# MAIN.net
KiCad netlist of a schematic drawn in Altium Designer
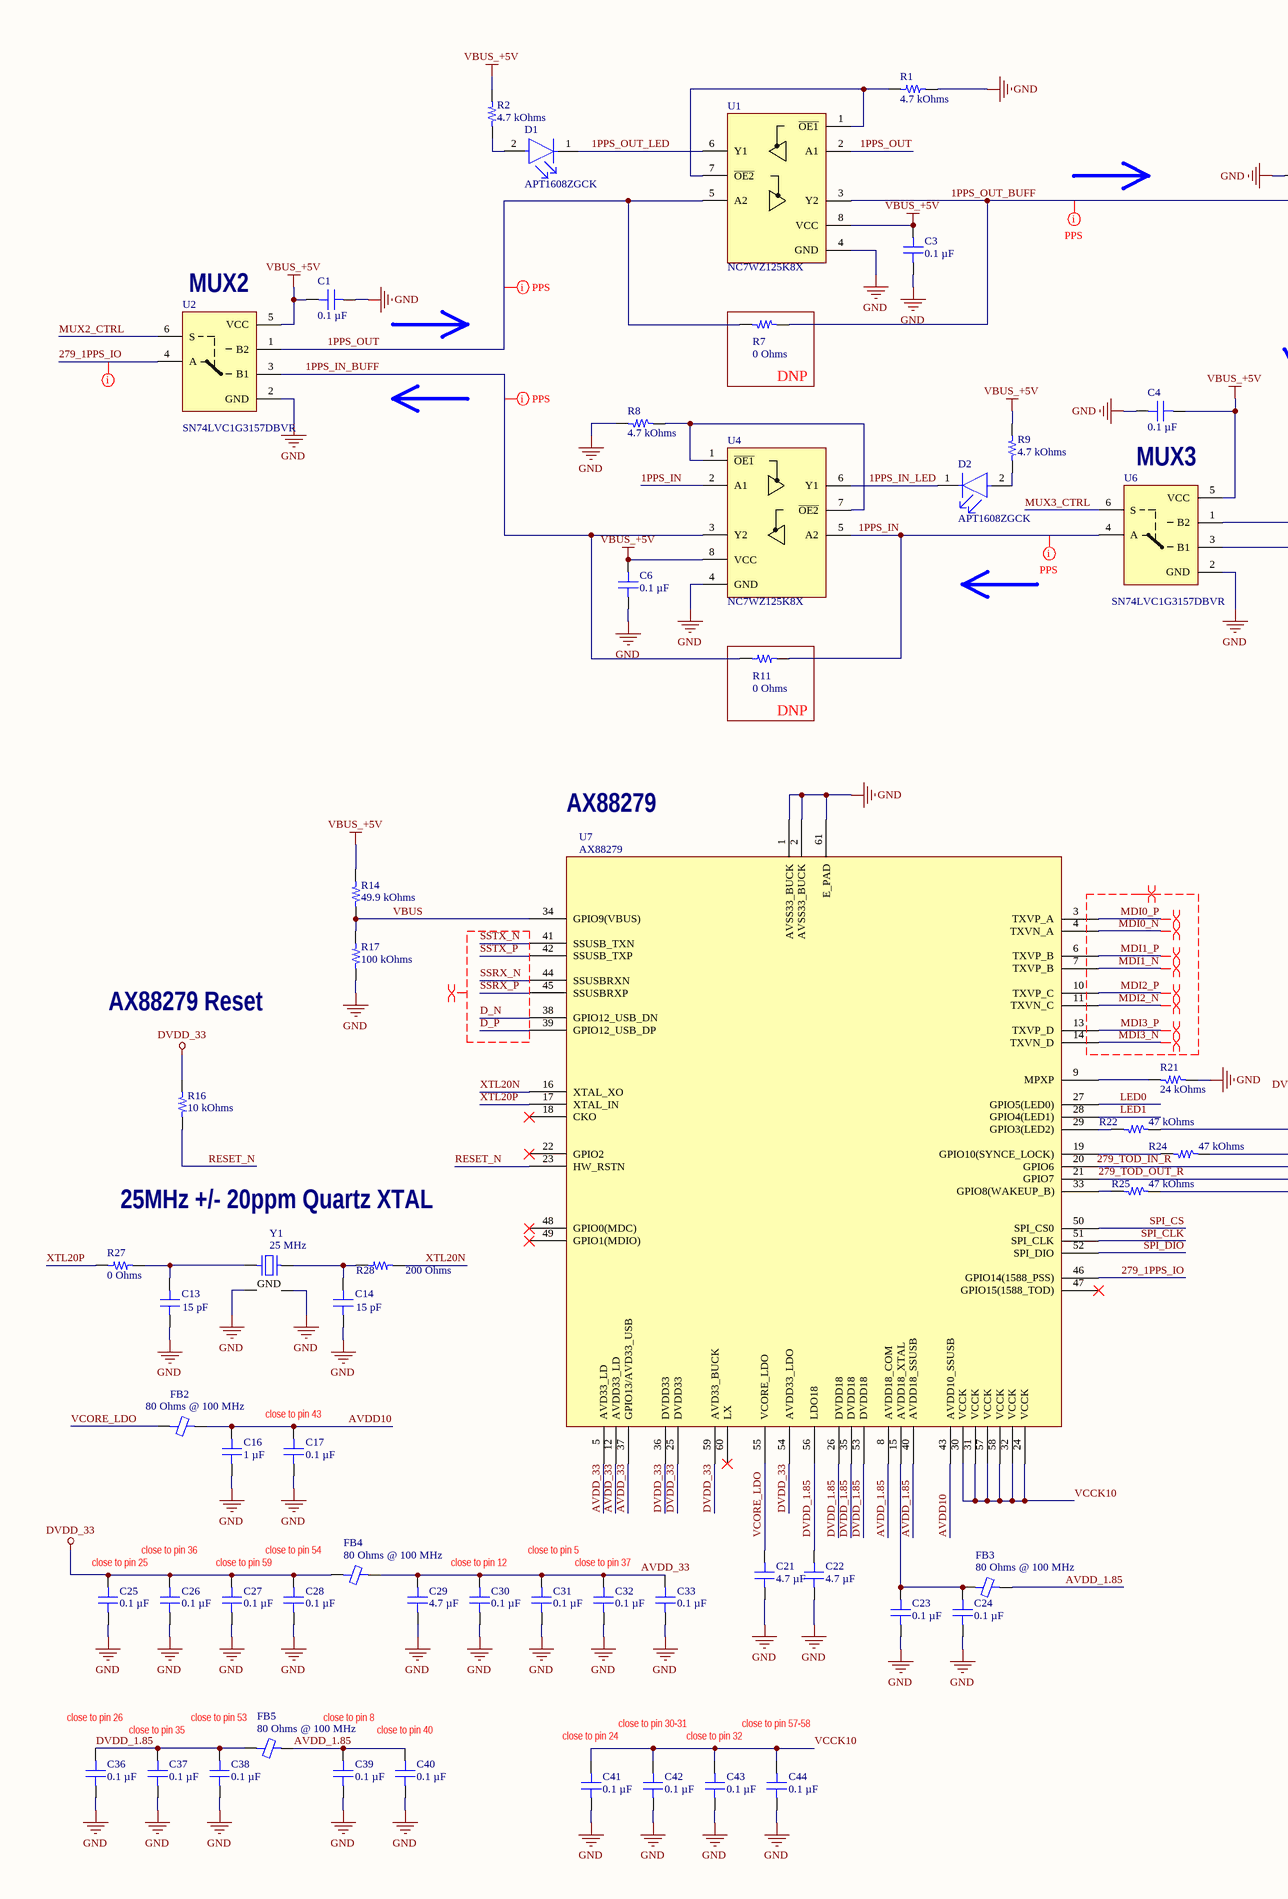
[diagram p0: MAIN.SchDoc, left]
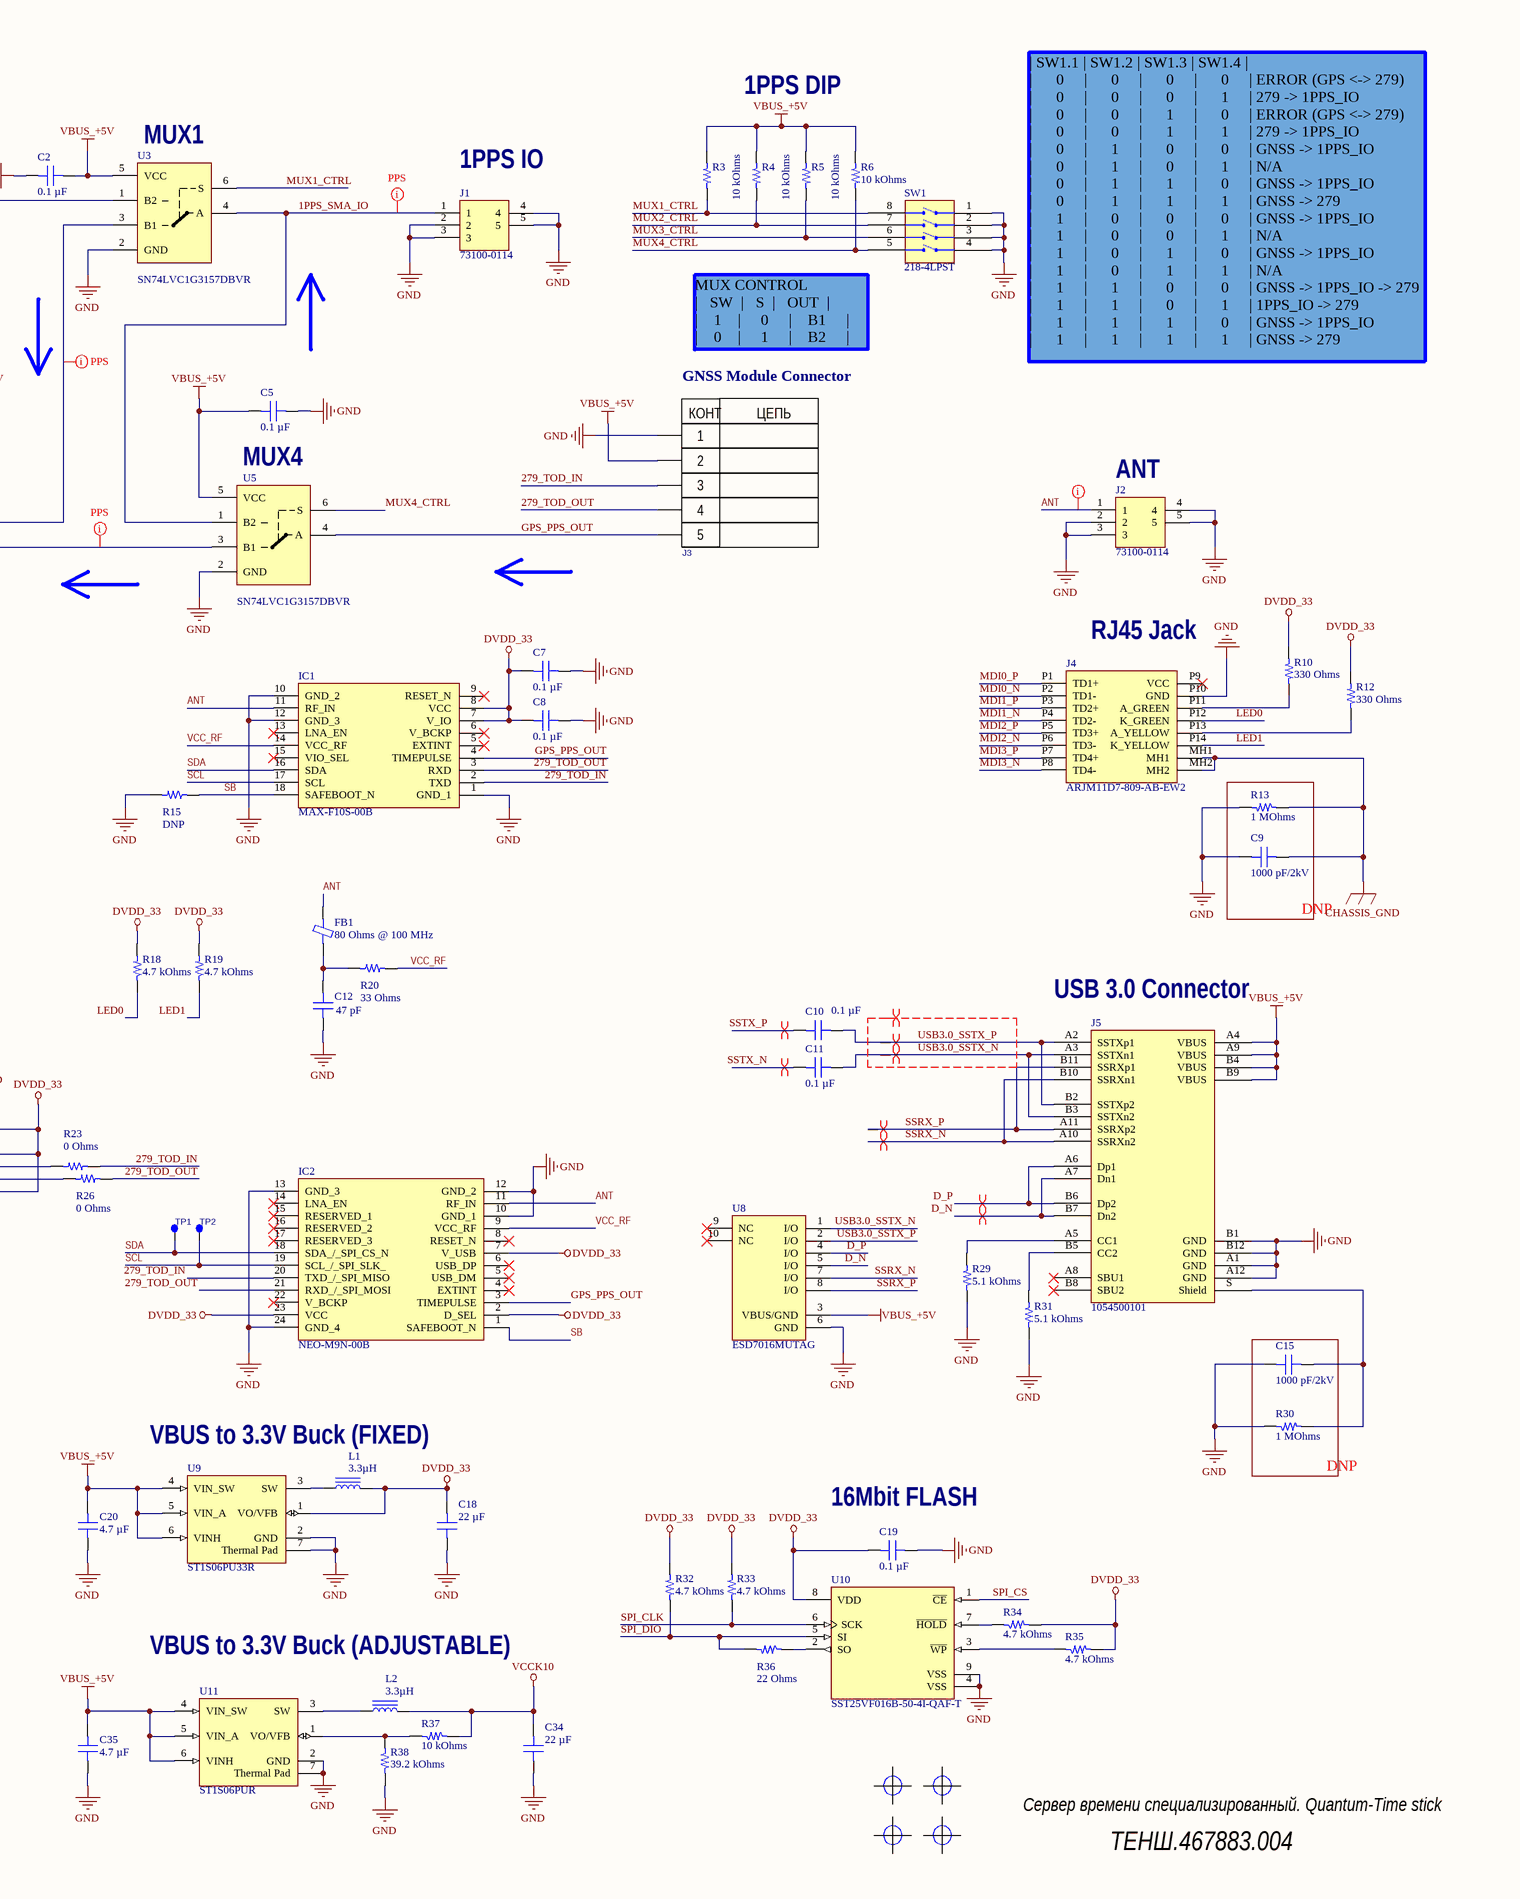
[diagram p1: MAIN.SchDoc, right]

(export (version "E")
  (design (tool "Eeschema 10.0.6"))
  (components
    (comp (ref "C1")
      (value "0.1 µF")
      (footprint "CAP 0402_1005")
      (description "CAP CER 0.1UF 10V X7R 0402")
      (fields (field (name "TOLERANCE") "±10%") (field (name "MANUFACTURER") "Yageo"))
      (libsource (lib "Celestial Altium Library - altium_library") (part "Capacitor"))
    )
    (comp (ref "C2")
      (value "0.1 µF")
      (footprint "CAP 0402_1005")
      (description "CAP CER 0.1UF 10V X7R 0402")
      (fields (field (name "TOLERANCE") "±10%") (field (name "MANUFACTURER") "Yageo"))
      (libsource (lib "Celestial Altium Library - altium_library") (part "Capacitor"))
    )
    (comp (ref "C3")
      (value "0.1 µF")
      (footprint "CAP 0402_1005")
      (description "CAP CER 0.1UF 10V X7R 0402")
      (fields (field (name "TOLERANCE") "±10%") (field (name "MANUFACTURER") "Yageo"))
      (libsource (lib "Celestial Altium Library - altium_library") (part "Capacitor"))
    )
    (comp (ref "C4")
      (value "0.1 µF")
      (footprint "CAP 0402_1005")
      (description "CAP CER 0.1UF 10V X7R 0402")
      (fields (field (name "TOLERANCE") "±10%") (field (name "MANUFACTURER") "Yageo"))
      (libsource (lib "Celestial Altium Library - altium_library") (part "Capacitor"))
    )
    (comp (ref "C5")
      (value "0.1 µF")
      (footprint "CAP 0402_1005")
      (description "CAP CER 0.1UF 10V X7R 0402")
      (fields (field (name "TOLERANCE") "±10%") (field (name "MANUFACTURER") "Yageo"))
      (libsource (lib "Celestial Altium Library - altium_library") (part "Capacitor"))
    )
    (comp (ref "C6")
      (value "0.1 µF")
      (footprint "CAP 0402_1005")
      (description "CAP CER 0.1UF 10V X7R 0402")
      (fields (field (name "TOLERANCE") "±10%") (field (name "MANUFACTURER") "Yageo"))
      (libsource (lib "Celestial Altium Library - altium_library") (part "Capacitor"))
    )
    (comp (ref "C7")
      (value "0.1 µF")
      (footprint "CAP 0402_1005")
      (description "CAP CER 0.1UF 10V X7R 0402")
      (fields (field (name "TOLERANCE") "±10%") (field (name "MANUFACTURER") "Yageo"))
      (libsource (lib "Celestial Altium Library - altium_library") (part "Capacitor"))
    )
    (comp (ref "C8")
      (value "0.1 µF")
      (footprint "CAP 0402_1005")
      (description "CAP CER 0.1UF 10V X7R 0402")
      (fields (field (name "TOLERANCE") "±10%") (field (name "MANUFACTURER") "Yageo"))
      (libsource (lib "Celestial Altium Library - altium_library") (part "Capacitor"))
    )
    (comp (ref "C9")
      (value "1000 pF/2kV")
      (footprint "CAP 1206_3216 - 0.8MM")
      (description "CAP CER 1000PF 2KV X7R 1206")
      (fields (field (name "PART NUMBER") "CC1206KKX7RDBB102") (field (name "MANUFACTURER") "Yageo"))
      (libsource (lib "Celestial Altium Library - altium_library") (part "Capacitor"))
    )
    (comp (ref "C10")
      (value "0.1 µF")
      (footprint "CAP 0402_1005")
      (description "CAP CER 0.1UF 10V X7R 0402")
      (fields (field (name "TOLERANCE") "±10%") (field (name "MANUFACTURER") "Yageo"))
      (libsource (lib "Celestial Altium Library - altium_library") (part "Capacitor"))
    )
    (comp (ref "C11")
      (value "0.1 µF")
      (footprint "CAP 0402_1005")
      (description "CAP CER 0.1UF 10V X7R 0402")
      (fields (field (name "TOLERANCE") "±10%") (field (name "MANUFACTURER") "Yageo"))
      (libsource (lib "Celestial Altium Library - altium_library") (part "Capacitor"))
    )
    (comp (ref "C12")
      (value "47 pF")
      (footprint "CAP 0402_1005")
      (description "CAP CER 47PF 50V C0G/NPO 0402")
      (fields (field (name "MANUFACTURER") "Yageo") (field (name "TOLERANCE") "±10%"))
      (libsource (lib "Celestial Altium Library - altium_library") (part "Capacitor"))
    )
    (comp (ref "C13")
      (value "15 pF")
      (footprint "CAP 0402_1005")
      (description "CAP CER 15PF 50V C0G/NPO 0402")
      (fields (field (name "MANUFACTURER") "Yageo") (field (name "TOLERANCE") "±10%"))
      (libsource (lib "Celestial Altium Library - altium_library") (part "Capacitor"))
    )
    (comp (ref "C14")
      (value "15 pF")
      (footprint "CAP 0402_1005")
      (description "CAP CER 15PF 50V C0G/NPO 0402")
      (fields (field (name "MANUFACTURER") "Yageo") (field (name "TOLERANCE") "±10%"))
      (libsource (lib "Celestial Altium Library - altium_library") (part "Capacitor"))
    )
    (comp (ref "C15")
      (value "1000 pF/2kV")
      (footprint "CAP 1206_3216 - 0.8MM")
      (description "CAP CER 1000PF 2KV X7R 1206")
      (fields (field (name "PART NUMBER") "CC1206KKX7RDBB102") (field (name "MANUFACTURER") "Yageo"))
      (libsource (lib "Celestial Altium Library - altium_library") (part "Capacitor"))
    )
    (comp (ref "C16")
      (value "1 µF")
      (footprint "CAP 0402_1005")
      (description "CAP CER 1UF 10V X5R 0402")
      (fields (field (name "TOLERANCE") "±10%") (field (name "MANUFACTURER") "Yageo"))
      (libsource (lib "Celestial Altium Library - altium_library") (part "Capacitor"))
    )
    (comp (ref "C17")
      (value "0.1 µF")
      (footprint "CAP 0402_1005")
      (description "CAP CER 0.1UF 10V X7R 0402")
      (fields (field (name "TOLERANCE") "±10%") (field (name "MANUFACTURER") "Yageo"))
      (libsource (lib "Celestial Altium Library - altium_library") (part "Capacitor"))
    )
    (comp (ref "C18")
      (value "22 µF")
      (footprint "CAP 0603_1608")
      (description "CAP CER 22UF 10V X5R 0603")
      (fields (field (name "MANUFACTURER") "Yageo") (field (name "TOLERANCE") "±20%"))
      (libsource (lib "Celestial Altium Library - altium_library") (part "Capacitor"))
    )
    (comp (ref "C19")
      (value "0.1 µF")
      (footprint "CAP 0402_1005")
      (description "CAP CER 0.1UF 10V X7R 0402")
      (fields (field (name "TOLERANCE") "±10%") (field (name "MANUFACTURER") "Yageo"))
      (libsource (lib "Celestial Altium Library - altium_library") (part "Capacitor"))
    )
    (comp (ref "C20")
      (value "4.7 µF")
      (footprint "CAP 0402_1005")
      (description "CAP CER 4.7UF 10V X5R 0402")
      (fields (field (name "TOLERANCE") "±20%") (field (name "MANUFACTURER") "Yageo"))
      (libsource (lib "Celestial Altium Library - altium_library") (part "Capacitor"))
    )
    (comp (ref "C21")
      (value "4.7 µF")
      (footprint "CAP 0402_1005")
      (description "CAP CER 4.7UF 10V X5R 0402")
      (fields (field (name "TOLERANCE") "±20%") (field (name "MANUFACTURER") "Yageo"))
      (libsource (lib "Celestial Altium Library - altium_library") (part "Capacitor"))
    )
    (comp (ref "C22")
      (value "4.7 µF")
      (footprint "CAP 0402_1005")
      (description "CAP CER 4.7UF 10V X5R 0402")
      (fields (field (name "TOLERANCE") "±20%") (field (name "MANUFACTURER") "Yageo"))
      (libsource (lib "Celestial Altium Library - altium_library") (part "Capacitor"))
    )
    (comp (ref "C23")
      (value "0.1 µF")
      (footprint "CAP 0402_1005")
      (description "CAP CER 0.1UF 10V X7R 0402")
      (fields (field (name "TOLERANCE") "±10%") (field (name "MANUFACTURER") "Yageo"))
      (libsource (lib "Celestial Altium Library - altium_library") (part "Capacitor"))
    )
    (comp (ref "C24")
      (value "0.1 µF")
      (footprint "CAP 0402_1005")
      (description "CAP CER 0.1UF 10V X7R 0402")
      (fields (field (name "TOLERANCE") "±10%") (field (name "MANUFACTURER") "Yageo"))
      (libsource (lib "Celestial Altium Library - altium_library") (part "Capacitor"))
    )
    (comp (ref "C25")
      (value "0.1 µF")
      (footprint "CAP 0402_1005")
      (description "CAP CER 0.1UF 10V X7R 0402")
      (fields (field (name "TOLERANCE") "±10%") (field (name "MANUFACTURER") "Yageo"))
      (libsource (lib "Celestial Altium Library - altium_library") (part "Capacitor"))
    )
    (comp (ref "C26")
      (value "0.1 µF")
      (footprint "CAP 0402_1005")
      (description "CAP CER 0.1UF 10V X7R 0402")
      (fields (field (name "TOLERANCE") "±10%") (field (name "MANUFACTURER") "Yageo"))
      (libsource (lib "Celestial Altium Library - altium_library") (part "Capacitor"))
    )
    (comp (ref "C27")
      (value "0.1 µF")
      (footprint "CAP 0402_1005")
      (description "CAP CER 0.1UF 10V X7R 0402")
      (fields (field (name "TOLERANCE") "±10%") (field (name "MANUFACTURER") "Yageo"))
      (libsource (lib "Celestial Altium Library - altium_library") (part "Capacitor"))
    )
    (comp (ref "C28")
      (value "0.1 µF")
      (footprint "CAP 0402_1005")
      (description "CAP CER 0.1UF 10V X7R 0402")
      (fields (field (name "TOLERANCE") "±10%") (field (name "MANUFACTURER") "Yageo"))
      (libsource (lib "Celestial Altium Library - altium_library") (part "Capacitor"))
    )
    (comp (ref "C29")
      (value "4.7 µF")
      (footprint "CAP 0402_1005")
      (description "CAP CER 4.7UF 10V X5R 0402")
      (fields (field (name "TOLERANCE") "±20%") (field (name "MANUFACTURER") "Yageo"))
      (libsource (lib "Celestial Altium Library - altium_library") (part "Capacitor"))
    )
    (comp (ref "C30")
      (value "0.1 µF")
      (footprint "CAP 0402_1005")
      (description "CAP CER 0.1UF 10V X7R 0402")
      (fields (field (name "TOLERANCE") "±10%") (field (name "MANUFACTURER") "Yageo"))
      (libsource (lib "Celestial Altium Library - altium_library") (part "Capacitor"))
    )
    (comp (ref "C31")
      (value "0.1 µF")
      (footprint "CAP 0402_1005")
      (description "CAP CER 0.1UF 10V X7R 0402")
      (fields (field (name "TOLERANCE") "±10%") (field (name "MANUFACTURER") "Yageo"))
      (libsource (lib "Celestial Altium Library - altium_library") (part "Capacitor"))
    )
    (comp (ref "C32")
      (value "0.1 µF")
      (footprint "CAP 0402_1005")
      (description "CAP CER 0.1UF 10V X7R 0402")
      (fields (field (name "TOLERANCE") "±10%") (field (name "MANUFACTURER") "Yageo"))
      (libsource (lib "Celestial Altium Library - altium_library") (part "Capacitor"))
    )
    (comp (ref "C33")
      (value "0.1 µF")
      (footprint "CAP 0402_1005")
      (description "CAP CER 0.1UF 10V X7R 0402")
      (fields (field (name "TOLERANCE") "±10%") (field (name "MANUFACTURER") "Yageo"))
      (libsource (lib "Celestial Altium Library - altium_library") (part "Capacitor"))
    )
    (comp (ref "C34")
      (value "22 µF")
      (footprint "CAP 0603_1608")
      (description "CAP CER 22UF 10V X5R 0603")
      (fields (field (name "MANUFACTURER") "Yageo") (field (name "TOLERANCE") "±20%"))
      (libsource (lib "Celestial Altium Library - altium_library") (part "Capacitor"))
    )
    (comp (ref "C35")
      (value "4.7 µF")
      (footprint "CAP 0402_1005")
      (description "CAP CER 4.7UF 10V X5R 0402")
      (fields (field (name "TOLERANCE") "±20%") (field (name "MANUFACTURER") "Yageo"))
      (libsource (lib "Celestial Altium Library - altium_library") (part "Capacitor"))
    )
    (comp (ref "C36")
      (value "0.1 µF")
      (footprint "CAP 0402_1005")
      (description "CAP CER 0.1UF 10V X7R 0402")
      (fields (field (name "TOLERANCE") "±10%") (field (name "MANUFACTURER") "Yageo"))
      (libsource (lib "Celestial Altium Library - altium_library") (part "Capacitor"))
    )
    (comp (ref "C37")
      (value "0.1 µF")
      (footprint "CAP 0402_1005")
      (description "CAP CER 0.1UF 10V X7R 0402")
      (fields (field (name "TOLERANCE") "±10%") (field (name "MANUFACTURER") "Yageo"))
      (libsource (lib "Celestial Altium Library - altium_library") (part "Capacitor"))
    )
    (comp (ref "C38")
      (value "0.1 µF")
      (footprint "CAP 0402_1005")
      (description "CAP CER 0.1UF 10V X7R 0402")
      (fields (field (name "TOLERANCE") "±10%") (field (name "MANUFACTURER") "Yageo"))
      (libsource (lib "Celestial Altium Library - altium_library") (part "Capacitor"))
    )
    (comp (ref "C39")
      (value "0.1 µF")
      (footprint "CAP 0402_1005")
      (description "CAP CER 0.1UF 10V X7R 0402")
      (fields (field (name "TOLERANCE") "±10%") (field (name "MANUFACTURER") "Yageo"))
      (libsource (lib "Celestial Altium Library - altium_library") (part "Capacitor"))
    )
    (comp (ref "C40")
      (value "0.1 µF")
      (footprint "CAP 0402_1005")
      (description "CAP CER 0.1UF 10V X7R 0402")
      (fields (field (name "TOLERANCE") "±10%") (field (name "MANUFACTURER") "Yageo"))
      (libsource (lib "Celestial Altium Library - altium_library") (part "Capacitor"))
    )
    (comp (ref "C41")
      (value "0.1 µF")
      (footprint "CAP 0402_1005")
      (description "CAP CER 0.1UF 10V X7R 0402")
      (fields (field (name "TOLERANCE") "±10%") (field (name "MANUFACTURER") "Yageo"))
      (libsource (lib "Celestial Altium Library - altium_library") (part "Capacitor"))
    )
    (comp (ref "C42")
      (value "0.1 µF")
      (footprint "CAP 0402_1005")
      (description "CAP CER 0.1UF 10V X7R 0402")
      (fields (field (name "TOLERANCE") "±10%") (field (name "MANUFACTURER") "Yageo"))
      (libsource (lib "Celestial Altium Library - altium_library") (part "Capacitor"))
    )
    (comp (ref "C43")
      (value "0.1 µF")
      (footprint "CAP 0402_1005")
      (description "CAP CER 0.1UF 10V X7R 0402")
      (fields (field (name "TOLERANCE") "±10%") (field (name "MANUFACTURER") "Yageo"))
      (libsource (lib "Celestial Altium Library - altium_library") (part "Capacitor"))
    )
    (comp (ref "C44")
      (value "0.1 µF")
      (footprint "CAP 0402_1005")
      (description "CAP CER 0.1UF 10V X7R 0402")
      (fields (field (name "TOLERANCE") "±10%") (field (name "MANUFACTURER") "Yageo"))
      (libsource (lib "Celestial Altium Library - altium_library") (part "Capacitor"))
    )
    (comp (ref "D1")
      (value "APT1608ZGCK")
      (footprint "FP-APT1608ZGCK-MFG")
      (description "LED GREEN CLEAR CHIP SMD")
      (fields (field (name "MANUFACTURER") "Kingbright"))
      (libsource (lib "Altium Content Vault") (part "8706943c75ba83719d021d2fdc84c58"))
    )
    (comp (ref "D2")
      (value "APT1608ZGCK")
      (footprint "FP-APT1608ZGCK-MFG")
      (description "LED GREEN CLEAR CHIP SMD")
      (fields (field (name "MANUFACTURER") "Kingbright"))
      (libsource (lib "Altium Content Vault") (part "8706943c75ba83719d021d2fdc84c58"))
    )
    (comp (ref "FB1")
      (value "80 Ohms @ 100 MHz")
      (footprint "FER 0402_1005")
      (description "FERRITE BEAD 80 OHM 0402 1LN")
      (fields
        (field (name "MANUFACTURER") "Murata Electronics")
        (field (name "PART NUMBER") "BLM15PD800SN1D")
      )
      (libsource (lib "Celestial Altium Library - altium_library") (part "Ferrite Chip"))
    )
    (comp (ref "FB2")
      (value "80 Ohms @ 100 MHz")
      (footprint "FER 0402_1005")
      (description "FERRITE BEAD 80 OHM 0402 1LN")
      (fields
        (field (name "MANUFACTURER") "Murata Electronics")
        (field (name "PART NUMBER") "BLM15PD800SN1D")
      )
      (libsource (lib "Celestial Altium Library - altium_library") (part "Ferrite Chip"))
    )
    (comp (ref "FB3")
      (value "80 Ohms @ 100 MHz")
      (footprint "FER 0402_1005")
      (description "FERRITE BEAD 80 OHM 0402 1LN")
      (fields
        (field (name "MANUFACTURER") "Murata Electronics")
        (field (name "PART NUMBER") "BLM15PD800SN1D")
      )
      (libsource (lib "Celestial Altium Library - altium_library") (part "Ferrite Chip"))
    )
    (comp (ref "FB4")
      (value "80 Ohms @ 100 MHz")
      (footprint "FER 0402_1005")
      (description "FERRITE BEAD 80 OHM 0402 1LN")
      (fields
        (field (name "MANUFACTURER") "Murata Electronics")
        (field (name "PART NUMBER") "BLM15PD800SN1D")
      )
      (libsource (lib "Celestial Altium Library - altium_library") (part "Ferrite Chip"))
    )
    (comp (ref "FB5")
      (value "80 Ohms @ 100 MHz")
      (footprint "FER 0402_1005")
      (description "FERRITE BEAD 80 OHM 0402 1LN")
      (fields
        (field (name "MANUFACTURER") "Murata Electronics")
        (field (name "PART NUMBER") "BLM15PD800SN1D")
      )
      (libsource (lib "Celestial Altium Library - altium_library") (part "Ferrite Chip"))
    )
    (comp (ref "IC1")
      (value "MAX-F10S-00B")
      (footprint "SamacSys:MAXF10S00B")
      (description "Integrated Circuit")
      (libsource (lib "SamacSys") (part "MAX-F10S-00B"))
    )
    (comp (ref "IC2")
      (value "NEO-M9N-00B")
      (footprint "SamacSys:NEOM9N00B")
      (description "Integrated Circuit")
      (fields (field (name "MOUSER PART NUMBER") "377-NEO-M9N-00B"))
      (libsource (lib "SamacSys") (part "NEO-M9N-00B"))
    )
    (comp (ref "J1")
      (value "73100-0114")
      (footprint "SamacSys:731000114")
      (description "Connector")
      (fields (field (name "MOUSER PART NUMBER") "538-73100-0114"))
      (libsource (lib "SamacSys") (part "73100-0114"))
    )
    (comp (ref "J2")
      (value "73100-0114")
      (footprint "SamacSys:731000114")
      (description "Connector")
      (fields (field (name "MOUSER PART NUMBER") "538-73100-0114"))
      (libsource (lib "SamacSys") (part "73100-0114"))
    )
    (comp (ref "J3")
      (value "PBS-5")
      (footprint "SamacSys:PBS-5")
      (description "Connector")
      (fields (field (name "MANUFACTURER") "Connfly") (field (name "PART NUMBER") "PBD-5"))
      (libsource (lib "SamacSys") (part "PBS-5"))
    )
    (comp (ref "J4")
      (value "ARJM11D7-809-AB-EW2")
      (footprint "SamacSys:ARJM11D7809ABEW2")
      (description "Connector")
      (fields (field (name "MOUSER PART NUMBER") "815-RJM11D7809ABEW2"))
      (libsource (lib "*") (part "ARJM11D7-809-AB-EW2"))
    )
    (comp (ref "J5")
      (value "1054500101")
      (footprint "Molex 1054500101")
      (description "CONN RCP USB3.1 TYPEC 24P SMD RA")
      (fields (field (name "MANUFACTURER") "Molex"))
      (libsource (lib "Celestial Altium Library - altium_library") (part "USB 3.0 Type C"))
    )
    (comp (ref "L1")
      (value "3.3µH")
      (footprint "IND 1008_2520")
      (description "FIXED IND 3.3UH 1.2A 100 MOHM")
      (fields (field (name "TOLERANCE") "±20%") (field (name "MANUFACTURER") "Murata Electronics"))
      (libsource (lib "Celestial Altium Library - altium_library") (part "Inductor"))
    )
    (comp (ref "L2")
      (value "3.3µH")
      (footprint "IND 1008_2520")
      (description "FIXED IND 3.3UH 1.2A 100 MOHM")
      (fields (field (name "TOLERANCE") "±20%") (field (name "MANUFACTURER") "Murata Electronics"))
      (libsource (lib "Celestial Altium Library - altium_library") (part "Inductor"))
    )
    (comp (ref "MNT1")
      (value "MOUNT_HOLE")
      (footprint "SamacSys:MOUNT_3mm")
      (description "Mount hole")
      (libsource (lib "SamacSys") (part "MOUNT_HOLE"))
    )
    (comp (ref "MNT2")
      (value "MOUNT_HOLE")
      (footprint "SamacSys:MOUNT_3mm")
      (description "Mount hole")
      (libsource (lib "SamacSys") (part "MOUNT_HOLE"))
    )
    (comp (ref "MNT3")
      (value "MOUNT_HOLE")
      (footprint "SamacSys:MOUNT_3mm")
      (description "Mount hole")
      (libsource (lib "SamacSys") (part "MOUNT_HOLE"))
    )
    (comp (ref "MNT4")
      (value "MOUNT_HOLE")
      (footprint "SamacSys:MOUNT_3mm")
      (description "Mount hole")
      (libsource (lib "SamacSys") (part "MOUNT_HOLE"))
    )
    (comp (ref "R1")
      (value "4.7 kOhms")
      (footprint "YAGEO RES 0402_1005")
      (description "RES 4.7K OHM 1% 1/16W 0402")
      (fields (field (name "TOLERANCE") "±1%") (field (name "MANUFACTURER") "Yageo"))
      (libsource (lib "Celestial Altium Library - altium_library") (part "Resistor"))
    )
    (comp (ref "R2")
      (value "4.7 kOhms")
      (footprint "YAGEO RES 0402_1005")
      (description "RES 4.7K OHM 1% 1/16W 0402")
      (fields (field (name "TOLERANCE") "±1%") (field (name "MANUFACTURER") "Yageo"))
      (libsource (lib "Celestial Altium Library - altium_library") (part "Resistor"))
    )
    (comp (ref "R3")
      (value "10 kOhms")
      (footprint "YAGEO RES 0402_1005")
      (description "RES 10K OHM 1% 1/16W 0402")
      (fields (field (name "TOLERANCE") "±1%") (field (name "MANUFACTURER") "Yageo"))
      (libsource (lib "Celestial Altium Library - altium_library") (part "Resistor"))
    )
    (comp (ref "R4")
      (value "10 kOhms")
      (footprint "YAGEO RES 0402_1005")
      (description "RES 10K OHM 1% 1/16W 0402")
      (fields (field (name "TOLERANCE") "±1%") (field (name "MANUFACTURER") "Yageo"))
      (libsource (lib "Celestial Altium Library - altium_library") (part "Resistor"))
    )
    (comp (ref "R5")
      (value "10 kOhms")
      (footprint "YAGEO RES 0402_1005")
      (description "RES 10K OHM 1% 1/16W 0402")
      (fields (field (name "TOLERANCE") "±1%") (field (name "MANUFACTURER") "Yageo"))
      (libsource (lib "Celestial Altium Library - altium_library") (part "Resistor"))
    )
    (comp (ref "R6")
      (value "10 kOhms")
      (footprint "YAGEO RES 0402_1005")
      (description "RES 10K OHM 1% 1/16W 0402")
      (fields (field (name "TOLERANCE") "±1%") (field (name "MANUFACTURER") "Yageo"))
      (libsource (lib "Celestial Altium Library - altium_library") (part "Resistor"))
    )
    (comp (ref "R7")
      (value "0 Ohms")
      (footprint "YAGEO RES 0402_1005")
      (description "RES 0 OHM JUMPER 1/16W 0402")
      (fields (field (name "TOLERANCE") "Jumper") (field (name "MANUFACTURER") "Yageo"))
      (libsource (lib "Celestial Altium Library - altium_library") (part "Resistor"))
    )
    (comp (ref "R8")
      (value "4.7 kOhms")
      (footprint "YAGEO RES 0402_1005")
      (description "RES 4.7K OHM 1% 1/16W 0402")
      (fields (field (name "TOLERANCE") "±1%") (field (name "MANUFACTURER") "Yageo"))
      (libsource (lib "Celestial Altium Library - altium_library") (part "Resistor"))
    )
    (comp (ref "R9")
      (value "4.7 kOhms")
      (footprint "YAGEO RES 0402_1005")
      (description "RES 4.7K OHM 1% 1/16W 0402")
      (fields (field (name "TOLERANCE") "±1%") (field (name "MANUFACTURER") "Yageo"))
      (libsource (lib "Celestial Altium Library - altium_library") (part "Resistor"))
    )
    (comp (ref "R10")
      (value "330 Ohms")
      (footprint "YAGEO RES 0402_1005")
      (description "RES 330 OHM 1% 1/16W 0402")
      (fields (field (name "TOLERANCE") "±1%") (field (name "MANUFACTURER") "Yageo"))
      (libsource (lib "Celestial Altium Library - altium_library") (part "Resistor"))
    )
    (comp (ref "R11")
      (value "0 Ohms")
      (footprint "YAGEO RES 0402_1005")
      (description "RES 0 OHM JUMPER 1/16W 0402")
      (fields (field (name "TOLERANCE") "Jumper") (field (name "MANUFACTURER") "Yageo"))
      (libsource (lib "Celestial Altium Library - altium_library") (part "Resistor"))
    )
    (comp (ref "R12")
      (value "330 Ohms")
      (footprint "YAGEO RES 0402_1005")
      (description "RES 330 OHM 1% 1/16W 0402")
      (fields (field (name "TOLERANCE") "±1%") (field (name "MANUFACTURER") "Yageo"))
      (libsource (lib "Celestial Altium Library - altium_library") (part "Resistor"))
    )
    (comp (ref "R13")
      (value "1 MOhms")
      (footprint "YAGEO RES 0402_1005")
      (description "RES 1M OHM 1% 1/16W 0402")
      (fields (field (name "TOLERANCE") "±1%") (field (name "MANUFACTURER") "Yageo"))
      (libsource (lib "Celestial Altium Library - altium_library") (part "Resistor"))
    )
    (comp (ref "R14")
      (value "49.9 kOhms")
      (footprint "YAGEO RES 0402_1005")
      (description "RES 49.9K OHM 1% 1/16W 0402")
      (fields (field (name "TOLERANCE") "±1%") (field (name "MANUFACTURER") "Yageo"))
      (libsource (lib "Celestial Altium Library - altium_library") (part "Resistor"))
    )
    (comp (ref "R15")
      (value "DNP")
      (footprint "YAGEO RES 0402_1005")
      (description "RES 0 OHM JUMPER 1/16W 0402")
      (fields (field (name "TOLERANCE") "Jumper") (field (name "MANUFACTURER") "Yageo"))
      (libsource (lib "Celestial Altium Library - altium_library") (part "Resistor"))
    )
    (comp (ref "R16")
      (value "10 kOhms")
      (footprint "YAGEO RES 0402_1005")
      (description "RES 10K OHM 1% 1/16W 0402")
      (fields (field (name "TOLERANCE") "±1%") (field (name "MANUFACTURER") "Yageo"))
      (libsource (lib "Celestial Altium Library - altium_library") (part "Resistor"))
    )
    (comp (ref "R17")
      (value "100 kOhms")
      (footprint "YAGEO RES 0402_1005")
      (description "RES 100K OHM 1% 1/16W 0402")
      (fields (field (name "TOLERANCE") "±1%") (field (name "MANUFACTURER") "Yageo"))
      (libsource (lib "Celestial Altium Library - altium_library") (part "Resistor"))
    )
    (comp (ref "R18")
      (value "4.7 kOhms")
      (footprint "YAGEO RES 0402_1005")
      (description "RES 4.7K OHM 1% 1/16W 0402")
      (fields (field (name "TOLERANCE") "±1%") (field (name "MANUFACTURER") "Yageo"))
      (libsource (lib "Celestial Altium Library - altium_library") (part "Resistor"))
    )
    (comp (ref "R19")
      (value "4.7 kOhms")
      (footprint "YAGEO RES 0402_1005")
      (description "RES 4.7K OHM 1% 1/16W 0402")
      (fields (field (name "TOLERANCE") "±1%") (field (name "MANUFACTURER") "Yageo"))
      (libsource (lib "Celestial Altium Library - altium_library") (part "Resistor"))
    )
    (comp (ref "R20")
      (value "33 Ohms")
      (footprint "YAGEO RES 0402_1005")
      (description "RES 33 OHM 1% 1/16W 0402")
      (fields (field (name "TOLERANCE") "±1%") (field (name "MANUFACTURER") "Yageo"))
      (libsource (lib "Celestial Altium Library - altium_library") (part "Resistor"))
    )
    (comp (ref "R21")
      (value "24 kOhms")
      (footprint "YAGEO RES 0402_1005")
      (description "RES 24K OHM 1% 1/16W 0402")
      (fields (field (name "TOLERANCE") "±1%") (field (name "MANUFACTURER") "Yageo"))
      (libsource (lib "Celestial Altium Library - altium_library") (part "Resistor"))
    )
    (comp (ref "R22")
      (value "47 kOhms")
      (footprint "YAGEO RES 0402_1005")
      (description "RES 47K OHM 1% 1/16W 0402")
      (fields (field (name "TOLERANCE") "±1%") (field (name "MANUFACTURER") "Yageo"))
      (libsource (lib "Celestial Altium Library - altium_library") (part "Resistor"))
    )
    (comp (ref "R23")
      (value "0 Ohms")
      (footprint "YAGEO RES 0402_1005")
      (description "RES 0 OHM JUMPER 1/16W 0402")
      (fields (field (name "TOLERANCE") "Jumper") (field (name "MANUFACTURER") "Yageo"))
      (libsource (lib "Celestial Altium Library - altium_library") (part "Resistor"))
    )
    (comp (ref "R24")
      (value "47 kOhms")
      (footprint "YAGEO RES 0402_1005")
      (description "RES 47K OHM 1% 1/16W 0402")
      (fields (field (name "TOLERANCE") "±1%") (field (name "MANUFACTURER") "Yageo"))
      (libsource (lib "Celestial Altium Library - altium_library") (part "Resistor"))
    )
    (comp (ref "R25")
      (value "47 kOhms")
      (footprint "YAGEO RES 0402_1005")
      (description "RES 47K OHM 1% 1/16W 0402")
      (fields (field (name "TOLERANCE") "±1%") (field (name "MANUFACTURER") "Yageo"))
      (libsource (lib "Celestial Altium Library - altium_library") (part "Resistor"))
    )
    (comp (ref "R26")
      (value "0 Ohms")
      (footprint "YAGEO RES 0402_1005")
      (description "RES 0 OHM JUMPER 1/16W 0402")
      (fields (field (name "TOLERANCE") "Jumper") (field (name "MANUFACTURER") "Yageo"))
      (libsource (lib "Celestial Altium Library - altium_library") (part "Resistor"))
    )
    (comp (ref "R27")
      (value "0 Ohms")
      (footprint "YAGEO RES 0402_1005")
      (description "RES 0 OHM JUMPER 1/16W 0402")
      (fields (field (name "TOLERANCE") "Jumper") (field (name "MANUFACTURER") "Yageo"))
      (libsource (lib "Celestial Altium Library - altium_library") (part "Resistor"))
    )
    (comp (ref "R28")
      (value "200 Ohms")
      (footprint "YAGEO RES 0402_1005")
      (description "RES 200 OHM 1% 1/16W 0402")
      (fields (field (name "MANUFACTURER") "Yageo") (field (name "PART NUMBER") "RC0402FR-07200RL"))
      (libsource (lib "Celestial Altium Library - altium_library") (part "Resistor"))
    )
    (comp (ref "R29")
      (value "5.1 kOhms")
      (footprint "YAGEO RES 0402_1005")
      (description "RES 5.1K OHM 1% 1/16W 0402")
      (fields (field (name "TOLERANCE") "±1%") (field (name "MANUFACTURER") "Yageo"))
      (libsource (lib "Celestial Altium Library - altium_library") (part "Resistor"))
    )
    (comp (ref "R30")
      (value "1 MOhms")
      (footprint "YAGEO RES 0402_1005")
      (description "RES 1M OHM 1% 1/16W 0402")
      (fields (field (name "TOLERANCE") "±1%") (field (name "MANUFACTURER") "Yageo"))
      (libsource (lib "Celestial Altium Library - altium_library") (part "Resistor"))
    )
    (comp (ref "R31")
      (value "5.1 kOhms")
      (footprint "YAGEO RES 0402_1005")
      (description "RES 5.1K OHM 1% 1/16W 0402")
      (fields (field (name "TOLERANCE") "±1%") (field (name "MANUFACTURER") "Yageo"))
      (libsource (lib "Celestial Altium Library - altium_library") (part "Resistor"))
    )
    (comp (ref "R32")
      (value "4.7 kOhms")
      (footprint "YAGEO RES 0402_1005")
      (description "RES 4.7K OHM 1% 1/16W 0402")
      (fields (field (name "TOLERANCE") "±1%") (field (name "MANUFACTURER") "Yageo"))
      (libsource (lib "Celestial Altium Library - altium_library") (part "Resistor"))
    )
    (comp (ref "R33")
      (value "4.7 kOhms")
      (footprint "YAGEO RES 0402_1005")
      (description "RES 4.7K OHM 1% 1/16W 0402")
      (fields (field (name "TOLERANCE") "±1%") (field (name "MANUFACTURER") "Yageo"))
      (libsource (lib "Celestial Altium Library - altium_library") (part "Resistor"))
    )
    (comp (ref "R34")
      (value "4.7 kOhms")
      (footprint "YAGEO RES 0402_1005")
      (description "RES 4.7K OHM 1% 1/16W 0402")
      (fields (field (name "TOLERANCE") "±1%") (field (name "MANUFACTURER") "Yageo"))
      (libsource (lib "Celestial Altium Library - altium_library") (part "Resistor"))
    )
    (comp (ref "R35")
      (value "4.7 kOhms")
      (footprint "YAGEO RES 0402_1005")
      (description "RES 4.7K OHM 1% 1/16W 0402")
      (fields (field (name "TOLERANCE") "±1%") (field (name "MANUFACTURER") "Yageo"))
      (libsource (lib "Celestial Altium Library - altium_library") (part "Resistor"))
    )
    (comp (ref "R36")
      (value "22 Ohms")
      (footprint "YAGEO RES 0402_1005")
      (description "RES 22 OHM 1% 1/16W 0402")
      (fields (field (name "TOLERANCE") "±1%") (field (name "MANUFACTURER") "Yageo"))
      (libsource (lib "Celestial Altium Library - altium_library") (part "Resistor"))
    )
    (comp (ref "R37")
      (value "10 kOhms")
      (footprint "YAGEO RES 0402_1005")
      (description "RES 10K OHM 1% 1/16W 0402")
      (fields (field (name "TOLERANCE") "±1%") (field (name "MANUFACTURER") "Yageo"))
      (libsource (lib "Celestial Altium Library - altium_library") (part "Resistor"))
    )
    (comp (ref "R38")
      (value "39.2 kOhms")
      (footprint "YAGEO RES 0402_1005")
      (description "RES 39.2K OHM 1% 1/16W 0402")
      (fields (field (name "TOLERANCE") "±1%") (field (name "MANUFACTURER") "Yageo"))
      (libsource (lib "Celestial Altium Library - altium_library") (part "Resistor"))
    )
    (comp (ref "SW1")
      (value "218-4LPST")
      (footprint "CTS 218-4LPJ")
      (description "SWITCH SLIDE DIP SPST 25MA 24V")
      (fields (field (name "MANUFACTURER") "CTS Electrocomponents"))
      (libsource (lib "Celestial Altium Library - altium_library") (part "DIP SW 4P"))
    )
    (comp (ref "TP1")
      (value "PAD_TEST")
      (footprint "Samacsys:PAD_TEST")
      (description "Test Point")
      (fields (field (name "TOLERANCE") "{Tolerance}") (field (name "MANUFACTURER") "{Manufacturer}"))
      (libsource (lib "SamacSys") (part "PAD_TEST"))
    )
    (comp (ref "TP2")
      (value "PAD_TEST")
      (footprint "Samacsys:PAD_TEST")
      (description "Test Point")
      (fields (field (name "TOLERANCE") "{Tolerance}") (field (name "MANUFACTURER") "{Manufacturer}"))
      (libsource (lib "SamacSys") (part "PAD_TEST"))
    )
    (comp (ref "U1")
      (value "NC7WZ125K8X")
      (footprint "SamacSys:SOP50P310X90-8N")
      (description "Integrated Circuit")
      (libsource (lib "SamacSys") (part "NC7WZ125K8X"))
    )
    (comp (ref "U2")
      (value "SN74LVC1G3157DBVR")
      (footprint "SamacSys:SOT95P280X145-6N")
      (description "Integrated Circuit")
      (fields (field (name "MOUSER PART NUMBER") "595-SN74LVC1G3157DBV"))
      (libsource (lib "SamacSys") (part "SN74LVC1G3157DBVR"))
    )
    (comp (ref "U3")
      (value "SN74LVC1G3157DBVR")
      (footprint "SamacSys:SOT95P280X145-6N")
      (description "Integrated Circuit")
      (fields (field (name "MOUSER PART NUMBER") "595-SN74LVC1G3157DBV"))
      (libsource (lib "") (part "SN74LVC1G3157DBVR_1"))
    )
    (comp (ref "U4")
      (value "NC7WZ125K8X")
      (footprint "SamacSys:SOP50P310X90-8N")
      (description "Integrated Circuit")
      (libsource (lib "") (part "NC7WZ125K8X_1"))
    )
    (comp (ref "U5")
      (value "SN74LVC1G3157DBVR")
      (footprint "SamacSys:SOT95P280X145-6N")
      (description "Integrated Circuit")
      (fields (field (name "MOUSER PART NUMBER") "595-SN74LVC1G3157DBV"))
      (libsource (lib "") (part "SN74LVC1G3157DBVR_1"))
    )
    (comp (ref "U6")
      (value "SN74LVC1G3157DBVR")
      (footprint "SamacSys:SOT95P280X145-6N")
      (description "Integrated Circuit")
      (fields (field (name "MOUSER PART NUMBER") "595-SN74LVC1G3157DBV"))
      (libsource (lib "SamacSys") (part "SN74LVC1G3157DBVR"))
    )
    (comp (ref "U7")
      (value "AX88279")
      (footprint "IC_AX88279")
      (libsource (lib "LotusSound") (part "IC_AX88279"))
    )
    (comp (ref "U8")
      (value "ESD7016MUTAG")
      (footprint "ONSC-UDFN-8-517CB_V")
      (description "Low Capacitance ESD Protection USB 3.0, 8-Pin UDFN, Pb-Free, Tape and Reel")
      (fields (field (name "MANUFACTURER") "On Semiconductor"))
      (libsource (lib "Altium Content Vault") (part "ONSC-ESD7016-UDFN-8-517CB"))
    )
    (comp (ref "U9")
      (value "ST1S06PU33R")
      (footprint "DFN6D_L")
      (fields (field (name "MANUFACTURER") "STMicroelectronics"))
      (libsource (lib "Altium Content Vault") (part "PM-DCDC-ST1S06-IL7"))
    )
    (comp (ref "U10")
      (value "SST25VF016B-50-4I-QAF-T")
      (footprint "FP-C04-452-MFG")
      (libsource (lib "Altium Content Vault") (part "d7313dde12fd16fde488169701056cc"))
    )
    (comp (ref "U11")
      (value "ST1S06PUR")
      (footprint "DFN6D_M")
      (libsource (lib "Altium Content Vault") (part "PM-DCDC-ST1S06-IL7"))
    )
    (comp (ref "Y1")
      (value "25 MHz")
      (footprint "NDK NX3225GA")
      (description "CRYSTAL 25.0000MHZ 8PF SMD")
      (fields
        (field (name "MANUFACTURER") "NDK America, Inc.")
        (field (name "PART NUMBER") "NX3225GA-25.000M-STD-CRG-2")
      )
      (libsource (lib "Celestial Altium Library - altium_library") (part "NDK Crystal NX3225GA"))
    )
  )
  (nets
    (net (code "1") (name "/1PPS_IN") (class "Default")
      (node (ref "R11") (pin "1") (pinfunction "1_1") (pintype "passive"))
      (node (ref "U4") (pin "2") (pinfunction "A1_2") (pintype "passive"))
      (node (ref "U4") (pin "5") (pinfunction "A2_5") (pintype "passive"))
      (node (ref "U6") (pin "4") (pinfunction "A_4") (pintype "passive"))
    )
    (net (code "2") (name "/1PPS_IN_BUFF") (class "Default")
      (node (ref "R11") (pin "2") (pinfunction "2_2") (pintype "passive"))
      (node (ref "U2") (pin "3") (pinfunction "B1_3") (pintype "passive"))
      (node (ref "U4") (pin "3") (pinfunction "Y2_3") (pintype "passive"))
    )
    (net (code "3") (name "/1PPS_IN_LED") (class "Default")
      (node (ref "D2") (pin "1") (pinfunction "C_1") (pintype "passive"))
      (node (ref "U4") (pin "6") (pinfunction "Y1_6") (pintype "passive"))
    )
    (net (code "4") (name "/1PPS_OUT") (class "Default")
      (node (ref "R7") (pin "2") (pinfunction "2_2") (pintype "passive"))
      (node (ref "U1") (pin "2") (pinfunction "A1_2") (pintype "passive"))
      (node (ref "U1") (pin "5") (pinfunction "A2_5") (pintype "passive"))
      (node (ref "U2") (pin "1") (pinfunction "B2_1") (pintype "passive"))
    )
    (net (code "5") (name "/1PPS_OUT_BUFF") (class "Default")
      (node (ref "R7") (pin "1") (pinfunction "1_1") (pintype "passive"))
      (node (ref "U1") (pin "3") (pinfunction "Y2_3") (pintype "passive"))
      (node (ref "U3") (pin "1") (pinfunction "B2_1") (pintype "passive"))
    )
    (net (code "6") (name "/1PPS_OUT_LED") (class "Default")
      (node (ref "D1") (pin "1") (pinfunction "C_1") (pintype "passive"))
      (node (ref "U1") (pin "6") (pinfunction "Y1_6") (pintype "passive"))
    )
    (net (code "7") (name "/1PPS_SMA_IO") (class "Default")
      (node (ref "J1") (pin "1") (pinfunction "1_1") (pintype "passive"))
      (node (ref "U3") (pin "4") (pinfunction "A_4") (pintype "passive"))
      (node (ref "U5") (pin "1") (pinfunction "B2_1") (pintype "passive"))
    )
    (net (code "8") (name "/279_1PPS_IO") (class "Default")
      (node (ref "U2") (pin "4") (pinfunction "A_4") (pintype "passive"))
      (node (ref "U7") (pin "46") (pinfunction "GPIO14(1588_PSS)_46") (pintype "passive"))
    )
    (net (code "9") (name "/279_TOD_IN") (class "Default")
      (node (ref "IC1") (pin "2") (pinfunction "TXD_2") (pintype "passive"))
      (node (ref "IC2") (pin "20") (pinfunction "TXD_/_SPI_MISO_20") (pintype "passive"))
      (node (ref "J3") (pin "3") (pinfunction "3_3") (pintype "passive"))
      (node (ref "R23") (pin "1") (pinfunction "1_1") (pintype "passive"))
    )
    (net (code "10") (name "/279_TOD_IN_R") (class "Default")
      (node (ref "R23") (pin "2") (pinfunction "2_2") (pintype "passive"))
      (node (ref "U7") (pin "20") (pinfunction "GPIO6_20") (pintype "passive"))
    )
    (net (code "11") (name "/279_TOD_OUT") (class "Default")
      (node (ref "IC1") (pin "3") (pinfunction "RXD_3") (pintype "passive"))
      (node (ref "IC2") (pin "21") (pinfunction "RXD_/_SPI_MOSI_21") (pintype "passive"))
      (node (ref "J3") (pin "4") (pinfunction "4_4") (pintype "passive"))
      (node (ref "R26") (pin "1") (pinfunction "1_1") (pintype "passive"))
    )
    (net (code "12") (name "/279_TOD_OUT_R") (class "Default")
      (node (ref "R26") (pin "2") (pinfunction "2_2") (pintype "passive"))
      (node (ref "U7") (pin "21") (pinfunction "GPIO7_21") (pintype "passive"))
    )
    (net (code "13") (name "/ANT") (class "Default")
      (node (ref "FB1") (pin "2") (pinfunction "2_2") (pintype "passive"))
      (node (ref "IC1") (pin "11") (pinfunction "RF_IN_11") (pintype "passive"))
      (node (ref "IC2") (pin "11") (pinfunction "RF_IN_11") (pintype "passive"))
      (node (ref "J2") (pin "1") (pinfunction "1_1") (pintype "passive"))
    )
    (net (code "14") (name "/AVDD10") (class "Default")
      (node (ref "C16") (pin "2") (pinfunction "2_2") (pintype "passive"))
      (node (ref "C17") (pin "2") (pinfunction "2_2") (pintype "passive"))
      (node (ref "FB2") (pin "2") (pinfunction "2_2") (pintype "passive"))
      (node (ref "U7") (pin "43") (pinfunction "AVDD10_SSUSB_43") (pintype "passive"))
    )
    (net (code "15") (name "/AVDD_1.85") (class "Default")
      (node (ref "C39") (pin "2") (pinfunction "2_2") (pintype "passive"))
      (node (ref "C40") (pin "2") (pinfunction "2_2") (pintype "passive"))
      (node (ref "FB3") (pin "2") (pinfunction "2_2") (pintype "passive"))
      (node (ref "FB5") (pin "2") (pinfunction "2_2") (pintype "passive"))
      (node (ref "U7") (pin "40") (pinfunction "AVDD18_SSUSB_40") (pintype "passive"))
      (node (ref "U7") (pin "8") (pinfunction "AVDD18_COM_8") (pintype "passive"))
    )
    (net (code "16") (name "/AVDD_33") (class "Default")
      (node (ref "C29") (pin "2") (pinfunction "2_2") (pintype "passive"))
      (node (ref "C30") (pin "2") (pinfunction "2_2") (pintype "passive"))
      (node (ref "C31") (pin "2") (pinfunction "2_2") (pintype "passive"))
      (node (ref "C32") (pin "2") (pinfunction "2_2") (pintype "passive"))
      (node (ref "C33") (pin "2") (pinfunction "2_2") (pintype "passive"))
      (node (ref "FB4") (pin "2") (pinfunction "2_2") (pintype "passive"))
      (node (ref "U7") (pin "12") (pinfunction "AVDD33_LD_12") (pintype "passive"))
      (node (ref "U7") (pin "37") (pinfunction "GPIO13/AVD33_USB_37") (pintype "passive"))
      (node (ref "U7") (pin "5") (pinfunction "AVD33_LD_5") (pintype "passive"))
    )
    (net (code "17") (name "/DVDD_1.85") (class "Default")
      (node (ref "C22") (pin "2") (pinfunction "2_2") (pintype "passive"))
      (node (ref "C36") (pin "2") (pinfunction "2_2") (pintype "passive"))
      (node (ref "C37") (pin "2") (pinfunction "2_2") (pintype "passive"))
      (node (ref "C38") (pin "2") (pinfunction "2_2") (pintype "passive"))
      (node (ref "FB5") (pin "1") (pinfunction "1_1") (pintype "passive"))
      (node (ref "U7") (pin "26") (pinfunction "DVDD18_26") (pintype "passive"))
      (node (ref "U7") (pin "35") (pinfunction "DVDD18_35") (pintype "passive"))
      (node (ref "U7") (pin "53") (pinfunction "DVDD18_53") (pintype "passive"))
      (node (ref "U7") (pin "56") (pinfunction "LDO18_56") (pintype "passive"))
    )
    (net (code "18") (name "/D_N") (class "Default")
      (node (ref "J5") (pin "A7") (pinfunction "Dn1_A7") (pintype "passive"))
      (node (ref "J5") (pin "B7") (pinfunction "Dn2_B7") (pintype "passive"))
      (node (ref "U7") (pin "38") (pinfunction "GPIO12_USB_DN_38") (pintype "passive"))
      (node (ref "U8") (pin "5") (pinfunction "I/O_5") (pintype "passive"))
    )
    (net (code "19") (name "/D_P") (class "Default")
      (node (ref "J5") (pin "A6") (pinfunction "Dp1_A6") (pintype "passive"))
      (node (ref "J5") (pin "B6") (pinfunction "Dp2_B6") (pintype "passive"))
      (node (ref "U7") (pin "39") (pinfunction "GPIO12_USB_DP_39") (pintype "passive"))
      (node (ref "U8") (pin "4") (pinfunction "I/O_4") (pintype "passive"))
    )
    (net (code "20") (name "/GPS_PPS_OUT") (class "Default")
      (node (ref "IC1") (pin "4") (pinfunction "TIMEPULSE_4") (pintype "passive"))
      (node (ref "IC2") (pin "3") (pinfunction "TIMEPULSE_3") (pintype "passive"))
      (node (ref "J3") (pin "5") (pinfunction "5_5") (pintype "passive"))
      (node (ref "U5") (pin "4") (pinfunction "A_4") (pintype "passive"))
    )
    (net (code "21") (name "/LED0") (class "Default")
      (node (ref "J4") (pin "P12") (pinfunction "K_GREEN_P12") (pintype "passive"))
      (node (ref "R18") (pin "2") (pinfunction "2_2") (pintype "passive"))
      (node (ref "U7") (pin "27") (pinfunction "GPIO5(LED0)_27") (pintype "passive"))
    )
    (net (code "22") (name "/LED1") (class "Default")
      (node (ref "J4") (pin "P14") (pinfunction "K_YELLOW_P14") (pintype "passive"))
      (node (ref "R19") (pin "2") (pinfunction "2_2") (pintype "passive"))
      (node (ref "U7") (pin "28") (pinfunction "GPIO4(LED1)_28") (pintype "passive"))
    )
    (net (code "23") (name "/MDI0_N") (class "Default")
      (node (ref "J4") (pin "P2") (pinfunction "TD1-_P2") (pintype "passive"))
      (node (ref "U7") (pin "4") (pinfunction "TXVN_A_4") (pintype "passive"))
    )
    (net (code "24") (name "/MDI0_P") (class "Default")
      (node (ref "J4") (pin "P1") (pinfunction "TD1+_P1") (pintype "passive"))
      (node (ref "U7") (pin "3") (pinfunction "TXVP_A_3") (pintype "passive"))
    )
    (net (code "25") (name "/MDI1_N") (class "Default")
      (node (ref "J4") (pin "P4") (pinfunction "TD2-_P4") (pintype "passive"))
      (node (ref "U7") (pin "7") (pinfunction "TXVP_B_7") (pintype "passive"))
    )
    (net (code "26") (name "/MDI1_P") (class "Default")
      (node (ref "J4") (pin "P3") (pinfunction "TD2+_P3") (pintype "passive"))
      (node (ref "U7") (pin "6") (pinfunction "TXVP_B_6") (pintype "passive"))
    )
    (net (code "27") (name "/MDI2_N") (class "Default")
      (node (ref "J4") (pin "P6") (pinfunction "TD3-_P6") (pintype "passive"))
      (node (ref "U7") (pin "11") (pinfunction "TXVN_C_11") (pintype "passive"))
    )
    (net (code "28") (name "/MDI2_P") (class "Default")
      (node (ref "J4") (pin "P5") (pinfunction "TD3+_P5") (pintype "passive"))
      (node (ref "U7") (pin "10") (pinfunction "TXVP_C_10") (pintype "passive"))
    )
    (net (code "29") (name "/MDI3_N") (class "Default")
      (node (ref "J4") (pin "P8") (pinfunction "TD4-_P8") (pintype "passive"))
      (node (ref "U7") (pin "14") (pinfunction "TXVN_D_14") (pintype "passive"))
    )
    (net (code "30") (name "/MDI3_P") (class "Default")
      (node (ref "J4") (pin "P7") (pinfunction "TD4+_P7") (pintype "passive"))
      (node (ref "U7") (pin "13") (pinfunction "TXVP_D_13") (pintype "passive"))
    )
    (net (code "31") (name "/MUX1_CTRL") (class "Default")
      (node (ref "R3") (pin "1") (pinfunction "1_1") (pintype "passive"))
      (node (ref "SW1") (pin "8") (pinfunction "8_8") (pintype "passive"))
      (node (ref "U3") (pin "6") (pinfunction "S_6") (pintype "passive"))
    )
    (net (code "32") (name "/MUX2_CTRL") (class "Default")
      (node (ref "R4") (pin "1") (pinfunction "1_1") (pintype "passive"))
      (node (ref "SW1") (pin "7") (pinfunction "7_7") (pintype "passive"))
      (node (ref "U2") (pin "6") (pinfunction "S_6") (pintype "passive"))
    )
    (net (code "33") (name "/MUX3_CTRL") (class "Default")
      (node (ref "R5") (pin "1") (pinfunction "1_1") (pintype "passive"))
      (node (ref "SW1") (pin "6") (pinfunction "6_6") (pintype "passive"))
      (node (ref "U6") (pin "6") (pinfunction "S_6") (pintype "passive"))
    )
    (net (code "34") (name "/MUX4_CTRL") (class "Default")
      (node (ref "R6") (pin "1") (pinfunction "1_1") (pintype "passive"))
      (node (ref "SW1") (pin "5") (pinfunction "5_5") (pintype "passive"))
      (node (ref "U5") (pin "6") (pinfunction "S_6") (pintype "passive"))
    )
    (net (code "35") (name "/RESET_N") (class "Default")
      (node (ref "R16") (pin "1") (pinfunction "1_1") (pintype "passive"))
      (node (ref "U7") (pin "23") (pinfunction "HW_RSTN_23") (pintype "passive"))
    )
    (net (code "36") (name "/SB") (class "Default")
      (node (ref "IC1") (pin "18") (pinfunction "SAFEBOOT_N_18") (pintype "passive"))
      (node (ref "IC2") (pin "1") (pinfunction "SAFEBOOT_N_1") (pintype "passive"))
      (node (ref "R15") (pin "1") (pinfunction "1_1") (pintype "passive"))
    )
    (net (code "37") (name "/SCL") (class "Default")
      (node (ref "IC1") (pin "17") (pinfunction "SCL_17") (pintype "passive"))
      (node (ref "IC2") (pin "19") (pinfunction "SCL_/_SPI_SLK__19") (pintype "passive"))
      (node (ref "TP2") (pin "1") (pinfunction "1_1") (pintype "passive"))
    )
    (net (code "38") (name "/SDA") (class "Default")
      (node (ref "IC1") (pin "16") (pinfunction "SDA_16") (pintype "passive"))
      (node (ref "IC2") (pin "18") (pinfunction "SDA_/_SPI_CS_N_18") (pintype "passive"))
      (node (ref "TP1") (pin "1") (pinfunction "1_1") (pintype "passive"))
    )
    (net (code "39") (name "/SPI_CLK") (class "Default")
      (node (ref "R33") (pin "2") (pinfunction "2_2") (pintype "passive"))
      (node (ref "U10") (pin "6") (pinfunction "SCK_6") (pintype "input"))
      (node (ref "U7") (pin "51") (pinfunction "SPI_CLK_51") (pintype "passive"))
    )
    (net (code "40") (name "/SPI_CS") (class "Default")
      (node (ref "U10") (pin "1") (pinfunction "~{CE}_1") (pintype "input"))
      (node (ref "U7") (pin "50") (pinfunction "SPI_CS0_50") (pintype "passive"))
    )
    (net (code "41") (name "/SPI_DIO") (class "Default")
      (node (ref "R32") (pin "2") (pinfunction "2_2") (pintype "passive"))
      (node (ref "R36") (pin "2") (pinfunction "2_2") (pintype "passive"))
      (node (ref "U10") (pin "5") (pinfunction "SI_5") (pintype "input"))
      (node (ref "U7") (pin "52") (pinfunction "SPI_DIO_52") (pintype "passive"))
    )
    (net (code "42") (name "/SSRX_N") (class "Default")
      (node (ref "J5") (pin "A10") (pinfunction "SSRXn2_A10") (pintype "passive"))
      (node (ref "J5") (pin "B10") (pinfunction "SSRXn1_B10") (pintype "passive"))
      (node (ref "U7") (pin "44") (pinfunction "SSUSBRXN_44") (pintype "passive"))
      (node (ref "U8") (pin "7") (pinfunction "I/O_7") (pintype "passive"))
    )
    (net (code "43") (name "/SSRX_P") (class "Default")
      (node (ref "J5") (pin "A11") (pinfunction "SSRXp2_A11") (pintype "passive"))
      (node (ref "J5") (pin "B11") (pinfunction "SSRXp1_B11") (pintype "passive"))
      (node (ref "U7") (pin "45") (pinfunction "SSUSBRXP_45") (pintype "passive"))
      (node (ref "U8") (pin "8") (pinfunction "I/O_8") (pintype "passive"))
    )
    (net (code "44") (name "/SSTX_N") (class "Default")
      (node (ref "C11") (pin "2") (pinfunction "2_2") (pintype "passive"))
      (node (ref "U7") (pin "41") (pinfunction "SSUSB_TXN_41") (pintype "passive"))
    )
    (net (code "45") (name "/SSTX_P") (class "Default")
      (node (ref "C10") (pin "2") (pinfunction "2_2") (pintype "passive"))
      (node (ref "U7") (pin "42") (pinfunction "SSUSB_TXP_42") (pintype "passive"))
    )
    (net (code "46") (name "/USB3.0_SSTX_N") (class "Default")
      (node (ref "C11") (pin "1") (pinfunction "1_1") (pintype "passive"))
      (node (ref "J5") (pin "A3") (pinfunction "SSTXn1_A3") (pintype "passive"))
      (node (ref "J5") (pin "B3") (pinfunction "SSTXn2_B3") (pintype "passive"))
      (node (ref "U8") (pin "1") (pinfunction "I/O_1") (pintype "passive"))
    )
    (net (code "47") (name "/USB3.0_SSTX_P") (class "Default")
      (node (ref "C10") (pin "1") (pinfunction "1_1") (pintype "passive"))
      (node (ref "J5") (pin "A2") (pinfunction "SSTXp1_A2") (pintype "passive"))
      (node (ref "J5") (pin "B2") (pinfunction "SSTXp2_B2") (pintype "passive"))
      (node (ref "U8") (pin "2") (pinfunction "I/O_2") (pintype "passive"))
    )
    (net (code "48") (name "/VBUS") (class "Default")
      (node (ref "R14") (pin "1") (pinfunction "1_1") (pintype "passive"))
      (node (ref "R17") (pin "2") (pinfunction "2_2") (pintype "passive"))
      (node (ref "U7") (pin "34") (pinfunction "GPIO9(VBUS)_34") (pintype "passive"))
    )
    (net (code "49") (name "/VCC_RF") (class "Default")
      (node (ref "IC1") (pin "14") (pinfunction "VCC_RF_14") (pintype "passive"))
      (node (ref "IC2") (pin "9") (pinfunction "VCC_RF_9") (pintype "passive"))
      (node (ref "R20") (pin "1") (pinfunction "1_1") (pintype "passive"))
    )
    (net (code "50") (name "/VCORE_LDO") (class "Default")
      (node (ref "C21") (pin "2") (pinfunction "2_2") (pintype "passive"))
      (node (ref "FB2") (pin "1") (pinfunction "1_1") (pintype "passive"))
      (node (ref "U7") (pin "55") (pinfunction "VCORE_LDO_55") (pintype "passive"))
    )
    (net (code "51") (name "/XTL20N") (class "Default")
      (node (ref "R28") (pin "2") (pinfunction "2_2") (pintype "passive"))
      (node (ref "U7") (pin "16") (pinfunction "XTAL_XO_16") (pintype "passive"))
    )
    (net (code "52") (name "/XTL20P") (class "Default")
      (node (ref "R27") (pin "2") (pinfunction "2_2") (pintype "passive"))
      (node (ref "U7") (pin "17") (pinfunction "XTAL_IN_17") (pintype "passive"))
    )
    (net (code "53") (name "CHASSIS_GND") (class "Default")
      (node (ref "C9") (pin "1") (pinfunction "1_1") (pintype "passive"))
      (node (ref "J4") (pin "MH1") (pinfunction "MH1_MH1") (pintype "passive"))
      (node (ref "J4") (pin "MH2") (pinfunction "MH2_MH2") (pintype "passive"))
      (node (ref "R13") (pin "1") (pinfunction "1_1") (pintype "passive"))
    )
    (net (code "54") (name "DVDD_33") (class "Default")
      (node (ref "C18") (pin "2") (pinfunction "2_2") (pintype "passive"))
      (node (ref "C19") (pin "2") (pinfunction "2_2") (pintype "passive"))
      (node (ref "C25") (pin "2") (pinfunction "2_2") (pintype "passive"))
      (node (ref "C26") (pin "2") (pinfunction "2_2") (pintype "passive"))
      (node (ref "C27") (pin "2") (pinfunction "2_2") (pintype "passive"))
      (node (ref "C28") (pin "2") (pinfunction "2_2") (pintype "passive"))
      (node (ref "C7") (pin "2") (pinfunction "2_2") (pintype "passive"))
      (node (ref "C8") (pin "2") (pinfunction "2_2") (pintype "passive"))
      (node (ref "FB4") (pin "1") (pinfunction "1_1") (pintype "passive"))
      (node (ref "IC1") (pin "7") (pinfunction "V_IO_7") (pintype "passive"))
      (node (ref "IC1") (pin "8") (pinfunction "VCC_8") (pintype "passive"))
      (node (ref "IC2") (pin "2") (pinfunction "D_SEL_2") (pintype "passive"))
      (node (ref "IC2") (pin "23") (pinfunction "VCC_23") (pintype "passive"))
      (node (ref "IC2") (pin "7") (pinfunction "V_USB_7") (pintype "passive"))
      (node (ref "L1") (pin "2") (pinfunction "2_2") (pintype "passive"))
      (node (ref "R10") (pin "2") (pinfunction "2_2") (pintype "passive"))
      (node (ref "R12") (pin "2") (pinfunction "2_2") (pintype "passive"))
      (node (ref "R16") (pin "2") (pinfunction "2_2") (pintype "passive"))
      (node (ref "R18") (pin "1") (pinfunction "1_1") (pintype "passive"))
      (node (ref "R19") (pin "1") (pinfunction "1_1") (pintype "passive"))
      (node (ref "R22") (pin "2") (pinfunction "2_2") (pintype "passive"))
      (node (ref "R24") (pin "2") (pinfunction "2_2") (pintype "passive"))
      (node (ref "R25") (pin "2") (pinfunction "2_2") (pintype "passive"))
      (node (ref "R32") (pin "1") (pinfunction "1_1") (pintype "passive"))
      (node (ref "R33") (pin "1") (pinfunction "1_1") (pintype "passive"))
      (node (ref "R34") (pin "1") (pinfunction "1_1") (pintype "passive"))
      (node (ref "R35") (pin "1") (pinfunction "1_1") (pintype "passive"))
      (node (ref "U10") (pin "8") (pinfunction "VDD_8") (pintype "power_in"))
      (node (ref "U7") (pin "25") (pinfunction "DVDD33_25") (pintype "passive"))
      (node (ref "U7") (pin "36") (pinfunction "DVDD33_36") (pintype "passive"))
      (node (ref "U7") (pin "54") (pinfunction "AVDD33_LDO_54") (pintype "passive"))
      (node (ref "U7") (pin "59") (pinfunction "AVD33_BUCK_59") (pintype "passive"))
      (node (ref "U9") (pin "1") (pinfunction "VO/VFB_1") (pintype "bidirectional"))
    )
    (net (code "55") (name "GND") (class "Default")
      (node (ref "C1") (pin "1") (pinfunction "1_1") (pintype "passive"))
      (node (ref "C12") (pin "1") (pinfunction "1_1") (pintype "passive"))
      (node (ref "C13") (pin "1") (pinfunction "1_1") (pintype "passive"))
      (node (ref "C14") (pin "1") (pinfunction "1_1") (pintype "passive"))
      (node (ref "C15") (pin "1") (pinfunction "1_1") (pintype "passive"))
      (node (ref "C16") (pin "1") (pinfunction "1_1") (pintype "passive"))
      (node (ref "C17") (pin "1") (pinfunction "1_1") (pintype "passive"))
      (node (ref "C18") (pin "1") (pinfunction "1_1") (pintype "passive"))
      (node (ref "C19") (pin "1") (pinfunction "1_1") (pintype "passive"))
      (node (ref "C2") (pin "1") (pinfunction "1_1") (pintype "passive"))
      (node (ref "C20") (pin "1") (pinfunction "1_1") (pintype "passive"))
      (node (ref "C21") (pin "1") (pinfunction "1_1") (pintype "passive"))
      (node (ref "C22") (pin "1") (pinfunction "1_1") (pintype "passive"))
      (node (ref "C23") (pin "1") (pinfunction "1_1") (pintype "passive"))
      (node (ref "C24") (pin "1") (pinfunction "1_1") (pintype "passive"))
      (node (ref "C25") (pin "1") (pinfunction "1_1") (pintype "passive"))
      (node (ref "C26") (pin "1") (pinfunction "1_1") (pintype "passive"))
      (node (ref "C27") (pin "1") (pinfunction "1_1") (pintype "passive"))
      (node (ref "C28") (pin "1") (pinfunction "1_1") (pintype "passive"))
      (node (ref "C29") (pin "1") (pinfunction "1_1") (pintype "passive"))
      (node (ref "C3") (pin "1") (pinfunction "1_1") (pintype "passive"))
      (node (ref "C30") (pin "1") (pinfunction "1_1") (pintype "passive"))
      (node (ref "C31") (pin "1") (pinfunction "1_1") (pintype "passive"))
      (node (ref "C32") (pin "1") (pinfunction "1_1") (pintype "passive"))
      (node (ref "C33") (pin "1") (pinfunction "1_1") (pintype "passive"))
      (node (ref "C34") (pin "1") (pinfunction "1_1") (pintype "passive"))
      (node (ref "C35") (pin "1") (pinfunction "1_1") (pintype "passive"))
      (node (ref "C36") (pin "1") (pinfunction "1_1") (pintype "passive"))
      (node (ref "C37") (pin "1") (pinfunction "1_1") (pintype "passive"))
      (node (ref "C38") (pin "1") (pinfunction "1_1") (pintype "passive"))
      (node (ref "C39") (pin "1") (pinfunction "1_1") (pintype "passive"))
      (node (ref "C4") (pin "1") (pinfunction "1_1") (pintype "passive"))
      (node (ref "C40") (pin "1") (pinfunction "1_1") (pintype "passive"))
      (node (ref "C41") (pin "1") (pinfunction "1_1") (pintype "passive"))
      (node (ref "C42") (pin "1") (pinfunction "1_1") (pintype "passive"))
      (node (ref "C43") (pin "1") (pinfunction "1_1") (pintype "passive"))
      (node (ref "C44") (pin "1") (pinfunction "1_1") (pintype "passive"))
      (node (ref "C5") (pin "1") (pinfunction "1_1") (pintype "passive"))
      (node (ref "C6") (pin "1") (pinfunction "1_1") (pintype "passive"))
      (node (ref "C7") (pin "1") (pinfunction "1_1") (pintype "passive"))
      (node (ref "C8") (pin "1") (pinfunction "1_1") (pintype "passive"))
      (node (ref "C9") (pin "2") (pinfunction "2_2") (pintype "passive"))
      (node (ref "IC1") (pin "1") (pinfunction "GND_1_1") (pintype "passive"))
      (node (ref "IC1") (pin "10") (pinfunction "GND_2_10") (pintype "passive"))
      (node (ref "IC1") (pin "12") (pinfunction "GND_3_12") (pintype "passive"))
      (node (ref "IC2") (pin "10") (pinfunction "GND_1_10") (pintype "passive"))
      (node (ref "IC2") (pin "12") (pinfunction "GND_2_12") (pintype "passive"))
      (node (ref "IC2") (pin "13") (pinfunction "GND_3_13") (pintype "passive"))
      (node (ref "IC2") (pin "24") (pinfunction "GND_4_24") (pintype "passive"))
      (node (ref "J1") (pin "2") (pinfunction "2_2") (pintype "passive"))
      (node (ref "J1") (pin "3") (pinfunction "3_3") (pintype "passive"))
      (node (ref "J1") (pin "4") (pinfunction "4_4") (pintype "passive"))
      (node (ref "J1") (pin "5") (pinfunction "5_5") (pintype "passive"))
      (node (ref "J2") (pin "2") (pinfunction "2_2") (pintype "passive"))
      (node (ref "J2") (pin "3") (pinfunction "3_3") (pintype "passive"))
      (node (ref "J2") (pin "4") (pinfunction "4_4") (pintype "passive"))
      (node (ref "J2") (pin "5") (pinfunction "5_5") (pintype "passive"))
      (node (ref "J3") (pin "1") (pinfunction "1_1") (pintype "passive"))
      (node (ref "J4") (pin "P10") (pinfunction "GND_P10") (pintype "passive"))
      (node (ref "J5") (pin "A1") (pinfunction "GND_A1") (pintype "passive"))
      (node (ref "J5") (pin "A12") (pinfunction "GND_A12") (pintype "passive"))
      (node (ref "J5") (pin "B1") (pinfunction "GND_B1") (pintype "passive"))
      (node (ref "J5") (pin "B12") (pinfunction "GND_B12") (pintype "passive"))
      (node (ref "R1") (pin "2") (pinfunction "2_2") (pintype "passive"))
      (node (ref "R13") (pin "2") (pinfunction "2_2") (pintype "passive"))
      (node (ref "R15") (pin "2") (pinfunction "2_2") (pintype "passive"))
      (node (ref "R17") (pin "1") (pinfunction "1_1") (pintype "passive"))
      (node (ref "R21") (pin "1") (pinfunction "1_1") (pintype "passive"))
      (node (ref "R29") (pin "2") (pinfunction "2_2") (pintype "passive"))
      (node (ref "R30") (pin "1") (pinfunction "1_1") (pintype "passive"))
      (node (ref "R31") (pin "2") (pinfunction "2_2") (pintype "passive"))
      (node (ref "R38") (pin "2") (pinfunction "2_2") (pintype "passive"))
      (node (ref "R8") (pin "1") (pinfunction "1_1") (pintype "passive"))
      (node (ref "SW1") (pin "1") (pinfunction "GND_1") (pintype "passive"))
      (node (ref "SW1") (pin "2") (pinfunction "GND_2") (pintype "passive"))
      (node (ref "SW1") (pin "3") (pinfunction "GND_3") (pintype "passive"))
      (node (ref "SW1") (pin "4") (pinfunction "GND_4") (pintype "passive"))
      (node (ref "U1") (pin "4") (pinfunction "GND_4") (pintype "passive"))
      (node (ref "U10") (pin "4") (pinfunction "VSS_4") (pintype "power_in"))
      (node (ref "U10") (pin "9") (pinfunction "VSS_9") (pintype "power_in"))
      (node (ref "U11") (pin "2") (pinfunction "GND_2") (pintype "power_in"))
      (node (ref "U11") (pin "7") (pinfunction "Thermal_Pad_7") (pintype "power_in"))
      (node (ref "U2") (pin "2") (pinfunction "GND_2") (pintype "passive"))
      (node (ref "U3") (pin "2") (pinfunction "GND_2") (pintype "passive"))
      (node (ref "U4") (pin "4") (pinfunction "GND_4") (pintype "passive"))
      (node (ref "U5") (pin "2") (pinfunction "GND_2") (pintype "passive"))
      (node (ref "U6") (pin "2") (pinfunction "GND_2") (pintype "passive"))
      (node (ref "U7") (pin "1") (pinfunction "AVSS33_BUCK_1") (pintype "passive"))
      (node (ref "U7") (pin "2") (pinfunction "AVSS33_BUCK_2") (pintype "passive"))
      (node (ref "U7") (pin "61") (pinfunction "E_PAD_61") (pintype "passive"))
      (node (ref "U8") (pin "6") (pinfunction "GND_6") (pintype "power_in"))
      (node (ref "U9") (pin "2") (pinfunction "GND_2") (pintype "power_in"))
      (node (ref "U9") (pin "7") (pinfunction "Thermal_Pad_7") (pintype "power_in"))
      (node (ref "Y1") (pin "2") (pinfunction "GND_2") (pintype "passive"))
      (node (ref "Y1") (pin "4") (pinfunction "GND_4") (pintype "passive"))
    )
    (net (code "56") (name "Net-(C12-Pad2)") (class "Default")
      (node (ref "C12") (pin "2") (pinfunction "2_2") (pintype "passive"))
      (node (ref "FB1") (pin "1") (pinfunction "1_1") (pintype "passive"))
      (node (ref "R20") (pin "2") (pinfunction "2_2") (pintype "passive"))
    )
    (net (code "57") (name "Net-(C13-Pad2)") (class "Default")
      (node (ref "C13") (pin "2") (pinfunction "2_2") (pintype "passive"))
      (node (ref "R27") (pin "1") (pinfunction "1_1") (pintype "passive"))
      (node (ref "Y1") (pin "1") (pinfunction "1_1") (pintype "passive"))
    )
    (net (code "58") (name "Net-(C14-Pad2)") (class "Default")
      (node (ref "C14") (pin "2") (pinfunction "2_2") (pintype "passive"))
      (node (ref "R28") (pin "1") (pinfunction "1_1") (pintype "passive"))
      (node (ref "Y1") (pin "3") (pinfunction "3_3") (pintype "passive"))
    )
    (net (code "59") (name "Net-(D1-A)") (class "Default")
      (node (ref "D1") (pin "2") (pinfunction "A_2") (pintype "passive"))
      (node (ref "R2") (pin "1") (pinfunction "1_1") (pintype "passive"))
    )
    (net (code "60") (name "Net-(D2-A)") (class "Default")
      (node (ref "D2") (pin "2") (pinfunction "A_2") (pintype "passive"))
      (node (ref "R9") (pin "1") (pinfunction "1_1") (pintype "passive"))
    )
    (net (code "61") (name "Net-(J4-A_GREEN)") (class "Default")
      (node (ref "J4") (pin "P11") (pinfunction "A_GREEN_P11") (pintype "passive"))
      (node (ref "R10") (pin "1") (pinfunction "1_1") (pintype "passive"))
    )
    (net (code "62") (name "Net-(J4-A_YELLOW)") (class "Default")
      (node (ref "J4") (pin "P13") (pinfunction "A_YELLOW_P13") (pintype "passive"))
      (node (ref "R12") (pin "1") (pinfunction "1_1") (pintype "passive"))
    )
    (net (code "63") (name "Net-(J5-CC1)") (class "Default")
      (node (ref "J5") (pin "A5") (pinfunction "CC1_A5") (pintype "passive"))
      (node (ref "R29") (pin "1") (pinfunction "1_1") (pintype "passive"))
    )
    (net (code "64") (name "Net-(J5-CC2)") (class "Default")
      (node (ref "J5") (pin "B5") (pinfunction "CC2_B5") (pintype "passive"))
      (node (ref "R31") (pin "1") (pinfunction "1_1") (pintype "passive"))
    )
    (net (code "65") (name "Net-(J5-Shield)") (class "Default")
      (node (ref "C15") (pin "2") (pinfunction "2_2") (pintype "passive"))
      (node (ref "J5") (pin "S") (pinfunction "Shield_S") (pintype "passive"))
      (node (ref "R30") (pin "2") (pinfunction "2_2") (pintype "passive"))
    )
    (net (code "66") (name "Net-(U1-~{OE1})") (class "Default")
      (node (ref "R1") (pin "1") (pinfunction "1_1") (pintype "passive"))
      (node (ref "U1") (pin "1") (pinfunction "~{OE1}_1") (pintype "passive"))
      (node (ref "U1") (pin "7") (pinfunction "~{OE2}_7") (pintype "passive"))
    )
    (net (code "67") (name "Net-(U3-B1)") (class "Default")
      (node (ref "U3") (pin "3") (pinfunction "B1_3") (pintype "passive"))
      (node (ref "U6") (pin "1") (pinfunction "B2_1") (pintype "passive"))
    )
    (net (code "68") (name "Net-(U4-~{OE1})") (class "Default")
      (node (ref "R8") (pin "2") (pinfunction "2_2") (pintype "passive"))
      (node (ref "U4") (pin "1") (pinfunction "~{OE1}_1") (pintype "passive"))
      (node (ref "U4") (pin "7") (pinfunction "~{OE2}_7") (pintype "passive"))
    )
    (net (code "69") (name "Net-(U5-B1)") (class "Default")
      (node (ref "U5") (pin "3") (pinfunction "B1_3") (pintype "passive"))
      (node (ref "U6") (pin "3") (pinfunction "B1_3") (pintype "passive"))
    )
    (net (code "70") (name "Net-(U7-AVDD18_XTAL)") (class "Default")
      (node (ref "C23") (pin "2") (pinfunction "2_2") (pintype "passive"))
      (node (ref "C24") (pin "2") (pinfunction "2_2") (pintype "passive"))
      (node (ref "FB3") (pin "1") (pinfunction "1_1") (pintype "passive"))
      (node (ref "U7") (pin "15") (pinfunction "AVDD18_XTAL_15") (pintype "passive"))
    )
    (net (code "71") (name "Net-(U7-GPIO3(LED2))") (class "Default")
      (node (ref "R22") (pin "1") (pinfunction "1_1") (pintype "passive"))
      (node (ref "U7") (pin "29") (pinfunction "GPIO3(LED2)_29") (pintype "passive"))
    )
    (net (code "72") (name "Net-(U7-GPIO8(WAKEUP_B))") (class "Default")
      (node (ref "R25") (pin "1") (pinfunction "1_1") (pintype "passive"))
      (node (ref "U7") (pin "33") (pinfunction "GPIO8(WAKEUP_B)_33") (pintype "passive"))
    )
    (net (code "73") (name "Net-(U7-GPIO10(SYNCE_LOCK))") (class "Default")
      (node (ref "R24") (pin "1") (pinfunction "1_1") (pintype "passive"))
      (node (ref "U7") (pin "19") (pinfunction "GPIO10(SYNCE_LOCK)_19") (pintype "passive"))
    )
    (net (code "74") (name "Net-(U7-MPXP)") (class "Default")
      (node (ref "R21") (pin "2") (pinfunction "2_2") (pintype "passive"))
      (node (ref "U7") (pin "9") (pinfunction "MPXP_9") (pintype "passive"))
    )
    (net (code "75") (name "Net-(U9-SW)") (class "Default")
      (node (ref "L1") (pin "1") (pinfunction "1_1") (pintype "passive"))
      (node (ref "U9") (pin "3") (pinfunction "SW_3") (pintype "passive"))
    )
    (net (code "76") (name "Net-(U10-SO)") (class "Default")
      (node (ref "R36") (pin "1") (pinfunction "1_1") (pintype "passive"))
      (node (ref "U10") (pin "2") (pinfunction "SO_2") (pintype "output"))
    )
    (net (code "77") (name "Net-(U10-~{HOLD})") (class "Default")
      (node (ref "R34") (pin "2") (pinfunction "2_2") (pintype "passive"))
      (node (ref "U10") (pin "7") (pinfunction "~{HOLD}_7") (pintype "input"))
    )
    (net (code "78") (name "Net-(U10-~{WP})") (class "Default")
      (node (ref "R35") (pin "2") (pinfunction "2_2") (pintype "passive"))
      (node (ref "U10") (pin "3") (pinfunction "~{WP}_3") (pintype "input"))
    )
    (net (code "79") (name "Net-(U11-SW)") (class "Default")
      (node (ref "L2") (pin "1") (pinfunction "1_1") (pintype "passive"))
      (node (ref "U11") (pin "3") (pinfunction "SW_3") (pintype "passive"))
    )
    (net (code "80") (name "Net-(U11-VO{slash}VFB)") (class "Default")
      (node (ref "R37") (pin "2") (pinfunction "2_2") (pintype "passive"))
      (node (ref "R38") (pin "1") (pinfunction "1_1") (pintype "passive"))
      (node (ref "U11") (pin "1") (pinfunction "VO/VFB_1") (pintype "bidirectional"))
    )
    (net (code "81") (name "VBUS_+5V") (class "Default")
      (node (ref "C1") (pin "2") (pinfunction "2_2") (pintype "passive"))
      (node (ref "C2") (pin "2") (pinfunction "2_2") (pintype "passive"))
      (node (ref "C20") (pin "2") (pinfunction "2_2") (pintype "passive"))
      (node (ref "C3") (pin "2") (pinfunction "2_2") (pintype "passive"))
      (node (ref "C35") (pin "2") (pinfunction "2_2") (pintype "passive"))
      (node (ref "C4") (pin "2") (pinfunction "2_2") (pintype "passive"))
      (node (ref "C5") (pin "2") (pinfunction "2_2") (pintype "passive"))
      (node (ref "C6") (pin "2") (pinfunction "2_2") (pintype "passive"))
      (node (ref "J3") (pin "2") (pinfunction "2_2") (pintype "passive"))
      (node (ref "J5") (pin "A4") (pinfunction "VBUS_A4") (pintype "passive"))
      (node (ref "J5") (pin "A9") (pinfunction "VBUS_A9") (pintype "passive"))
      (node (ref "J5") (pin "B4") (pinfunction "VBUS_B4") (pintype "passive"))
      (node (ref "J5") (pin "B9") (pinfunction "VBUS_B9") (pintype "passive"))
      (node (ref "R14") (pin "2") (pinfunction "2_2") (pintype "passive"))
      (node (ref "R2") (pin "2") (pinfunction "2_2") (pintype "passive"))
      (node (ref "R3") (pin "2") (pinfunction "2_2") (pintype "passive"))
      (node (ref "R4") (pin "2") (pinfunction "2_2") (pintype "passive"))
      (node (ref "R5") (pin "2") (pinfunction "2_2") (pintype "passive"))
      (node (ref "R6") (pin "2") (pinfunction "2_2") (pintype "passive"))
      (node (ref "R9") (pin "2") (pinfunction "2_2") (pintype "passive"))
      (node (ref "U1") (pin "8") (pinfunction "VCC_8") (pintype "passive"))
      (node (ref "U11") (pin "4") (pinfunction "VIN_SW_4") (pintype "input"))
      (node (ref "U11") (pin "5") (pinfunction "VIN_A_5") (pintype "input"))
      (node (ref "U11") (pin "6") (pinfunction "VINH_6") (pintype "input"))
      (node (ref "U2") (pin "5") (pinfunction "VCC_5") (pintype "passive"))
      (node (ref "U3") (pin "5") (pinfunction "VCC_5") (pintype "passive"))
      (node (ref "U4") (pin "8") (pinfunction "VCC_8") (pintype "passive"))
      (node (ref "U5") (pin "5") (pinfunction "VCC_5") (pintype "passive"))
      (node (ref "U6") (pin "5") (pinfunction "VCC_5") (pintype "passive"))
      (node (ref "U8") (pin "3") (pinfunction "VBUS/GND_3") (pintype "power_in"))
      (node (ref "U9") (pin "4") (pinfunction "VIN_SW_4") (pintype "input"))
      (node (ref "U9") (pin "5") (pinfunction "VIN_A_5") (pintype "input"))
      (node (ref "U9") (pin "6") (pinfunction "VINH_6") (pintype "input"))
    )
    (net (code "82") (name "VCCK10") (class "Default")
      (node (ref "C34") (pin "2") (pinfunction "2_2") (pintype "passive"))
      (node (ref "C41") (pin "2") (pinfunction "2_2") (pintype "passive"))
      (node (ref "C42") (pin "2") (pinfunction "2_2") (pintype "passive"))
      (node (ref "C43") (pin "2") (pinfunction "2_2") (pintype "passive"))
      (node (ref "C44") (pin "2") (pinfunction "2_2") (pintype "passive"))
      (node (ref "L2") (pin "2") (pinfunction "2_2") (pintype "passive"))
      (node (ref "R37") (pin "1") (pinfunction "1_1") (pintype "passive"))
      (node (ref "U7") (pin "24") (pinfunction "VCCK_24") (pintype "passive"))
      (node (ref "U7") (pin "30") (pinfunction "VCCK_30") (pintype "passive"))
      (node (ref "U7") (pin "31") (pinfunction "VCCK_31") (pintype "passive"))
      (node (ref "U7") (pin "32") (pinfunction "VCCK_32") (pintype "passive"))
      (node (ref "U7") (pin "57") (pinfunction "VCCK_57") (pintype "passive"))
      (node (ref "U7") (pin "58") (pinfunction "VCCK_58") (pintype "passive"))
    )
    (net (code "83") (name "unconnected-(IC1-EXTINT-Pad5)") (class "Default")
      (node (ref "IC1") (pin "5") (pinfunction "EXTINT_5") (pintype "passive+no_connect"))
    )
    (net (code "84") (name "unconnected-(IC1-LNA_EN-Pad13)") (class "Default")
      (node (ref "IC1") (pin "13") (pinfunction "LNA_EN_13") (pintype "passive+no_connect"))
    )
    (net (code "85") (name "unconnected-(IC1-RESET_N-Pad9)") (class "Default")
      (node (ref "IC1") (pin "9") (pinfunction "RESET_N_9") (pintype "passive+no_connect"))
    )
    (net (code "86") (name "unconnected-(IC1-VIO_SEL-Pad15)") (class "Default")
      (node (ref "IC1") (pin "15") (pinfunction "VIO_SEL_15") (pintype "passive+no_connect"))
    )
    (net (code "87") (name "unconnected-(IC1-V_BCKP-Pad6)") (class "Default")
      (node (ref "IC1") (pin "6") (pinfunction "V_BCKP_6") (pintype "passive+no_connect"))
    )
    (net (code "88") (name "unconnected-(IC2-EXTINT-Pad4)") (class "Default")
      (node (ref "IC2") (pin "4") (pinfunction "EXTINT_4") (pintype "passive+no_connect"))
    )
    (net (code "89") (name "unconnected-(IC2-LNA_EN-Pad14)") (class "Default")
      (node (ref "IC2") (pin "14") (pinfunction "LNA_EN_14") (pintype "passive+no_connect"))
    )
    (net (code "90") (name "unconnected-(IC2-RESERVED_1-Pad15)") (class "Default")
      (node (ref "IC2") (pin "15") (pinfunction "RESERVED_1_15") (pintype "passive+no_connect"))
    )
    (net (code "91") (name "unconnected-(IC2-RESERVED_2-Pad16)") (class "Default")
      (node (ref "IC2") (pin "16") (pinfunction "RESERVED_2_16") (pintype "passive+no_connect"))
    )
    (net (code "92") (name "unconnected-(IC2-RESERVED_3-Pad17)") (class "Default")
      (node (ref "IC2") (pin "17") (pinfunction "RESERVED_3_17") (pintype "passive+no_connect"))
    )
    (net (code "93") (name "unconnected-(IC2-RESET_N-Pad8)") (class "Default")
      (node (ref "IC2") (pin "8") (pinfunction "RESET_N_8") (pintype "passive+no_connect"))
    )
    (net (code "94") (name "unconnected-(IC2-USB_DM-Pad5)") (class "Default")
      (node (ref "IC2") (pin "5") (pinfunction "USB_DM_5") (pintype "passive+no_connect"))
    )
    (net (code "95") (name "unconnected-(IC2-USB_DP-Pad6)") (class "Default")
      (node (ref "IC2") (pin "6") (pinfunction "USB_DP_6") (pintype "passive+no_connect"))
    )
    (net (code "96") (name "unconnected-(IC2-V_BCKP-Pad22)") (class "Default")
      (node (ref "IC2") (pin "22") (pinfunction "V_BCKP_22") (pintype "passive+no_connect"))
    )
    (net (code "97") (name "unconnected-(J4-VCC-PadP9)") (class "Default")
      (node (ref "J4") (pin "P9") (pinfunction "VCC_P9") (pintype "passive+no_connect"))
    )
    (net (code "98") (name "unconnected-(J5-SBU1-PadA8)") (class "Default")
      (node (ref "J5") (pin "A8") (pinfunction "SBU1_A8") (pintype "passive+no_connect"))
    )
    (net (code "99") (name "unconnected-(J5-SBU2-PadB8)") (class "Default")
      (node (ref "J5") (pin "B8") (pinfunction "SBU2_B8") (pintype "passive+no_connect"))
    )
    (net (code "100") (name "unconnected-(U7-CKO-Pad18)") (class "Default")
      (node (ref "U7") (pin "18") (pinfunction "CKO_18") (pintype "passive+no_connect"))
    )
    (net (code "101") (name "unconnected-(U7-GPIO0(MDC)-Pad48)") (class "Default")
      (node (ref "U7") (pin "48") (pinfunction "GPIO0(MDC)_48") (pintype "passive+no_connect"))
    )
    (net (code "102") (name "unconnected-(U7-GPIO1(MDIO)-Pad49)") (class "Default")
      (node (ref "U7") (pin "49") (pinfunction "GPIO1(MDIO)_49") (pintype "passive+no_connect"))
    )
    (net (code "103") (name "unconnected-(U7-GPIO2-Pad22)") (class "Default")
      (node (ref "U7") (pin "22") (pinfunction "GPIO2_22") (pintype "passive+no_connect"))
    )
    (net (code "104") (name "unconnected-(U7-GPIO15(1588_TOD)-Pad47)") (class "Default")
      (node (ref "U7") (pin "47") (pinfunction "GPIO15(1588_TOD)_47") (pintype "passive+no_connect"))
    )
    (net (code "105") (name "unconnected-(U7-LX-Pad60)") (class "Default")
      (node (ref "U7") (pin "60") (pinfunction "LX_60") (pintype "passive+no_connect"))
    )
    (net (code "106") (name "unconnected-(U8-NC-Pad9)") (class "Default")
      (node (ref "U8") (pin "9") (pinfunction "NC_9") (pintype "passive+no_connect"))
    )
    (net (code "107") (name "unconnected-(U8-NC-Pad10)") (class "Default")
      (node (ref "U8") (pin "10") (pinfunction "NC_10") (pintype "passive+no_connect"))
    )
  )
)
